# v2.net
KiCad netlist of a schematic drawn in EAGLE
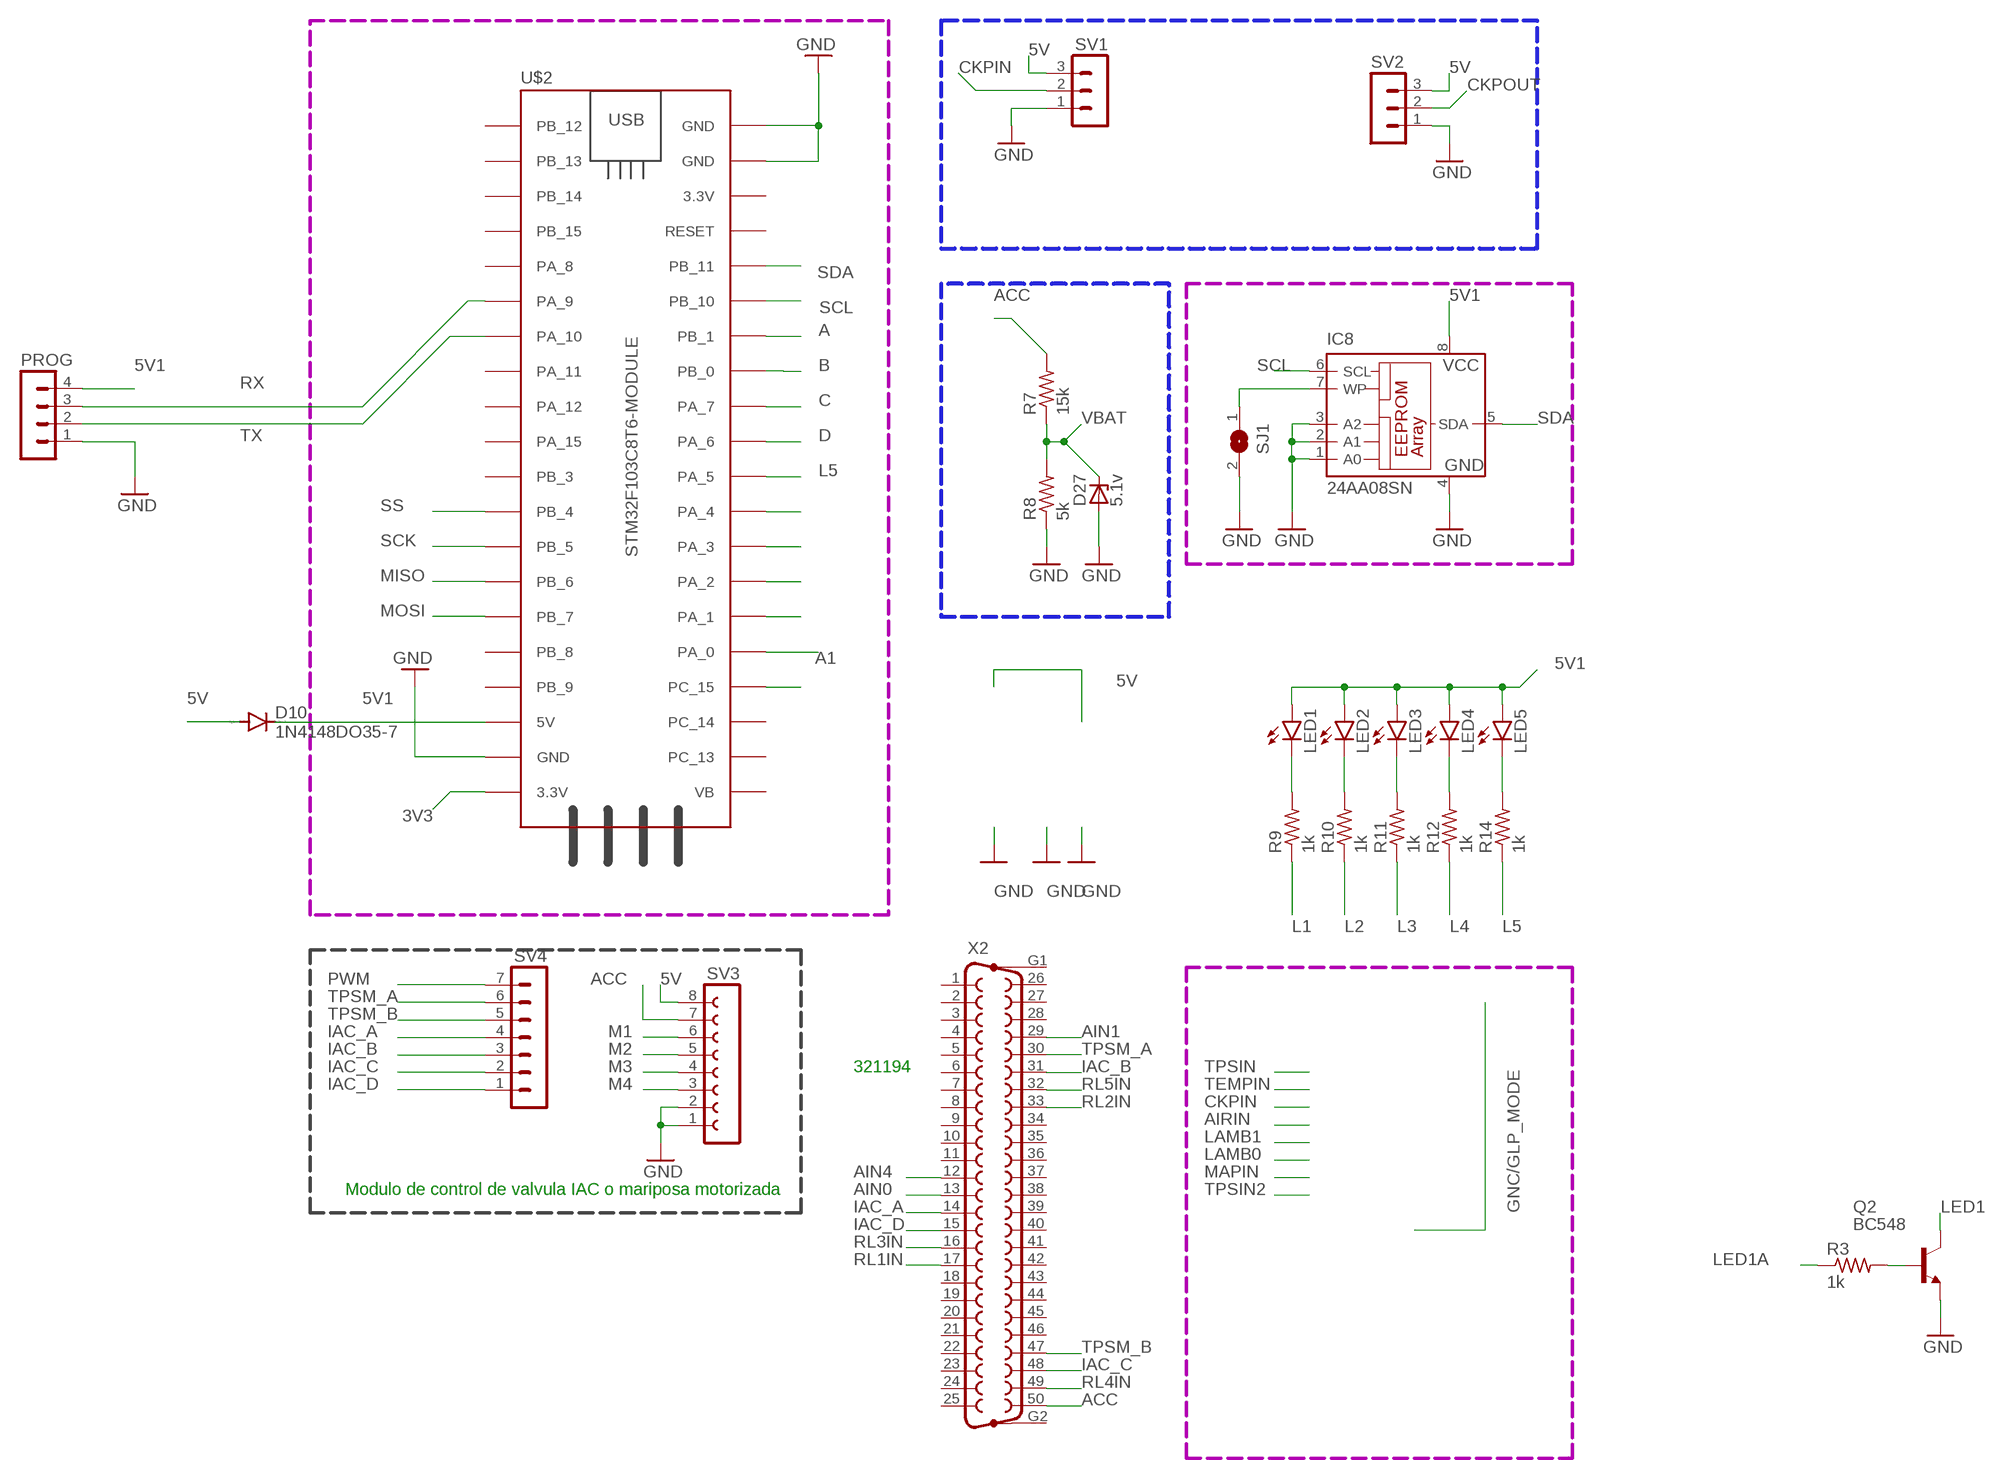
[diagram p0: schematic, sheet 1]
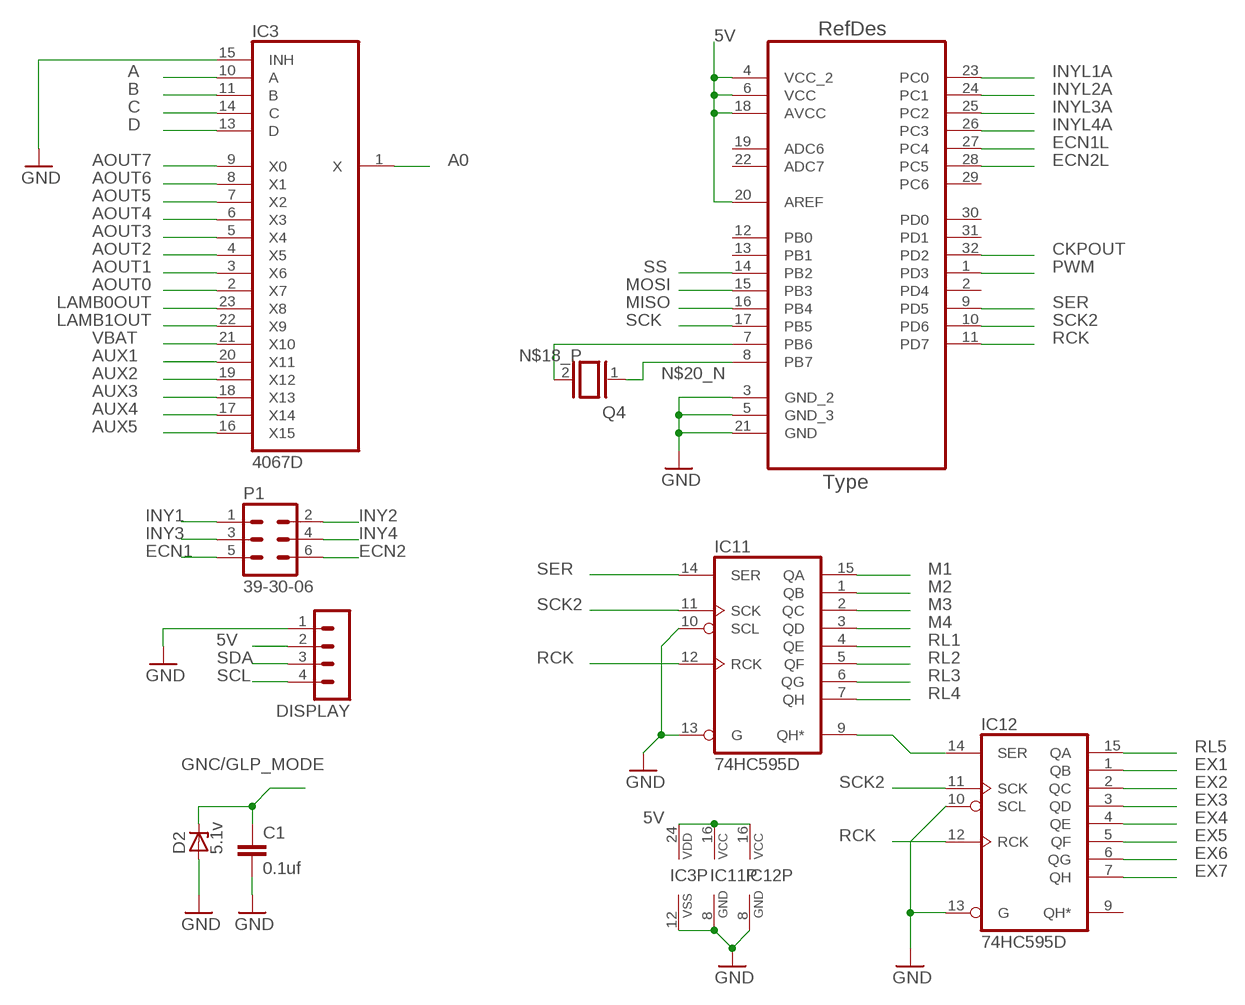
[diagram p1: schematic, sheet 2]
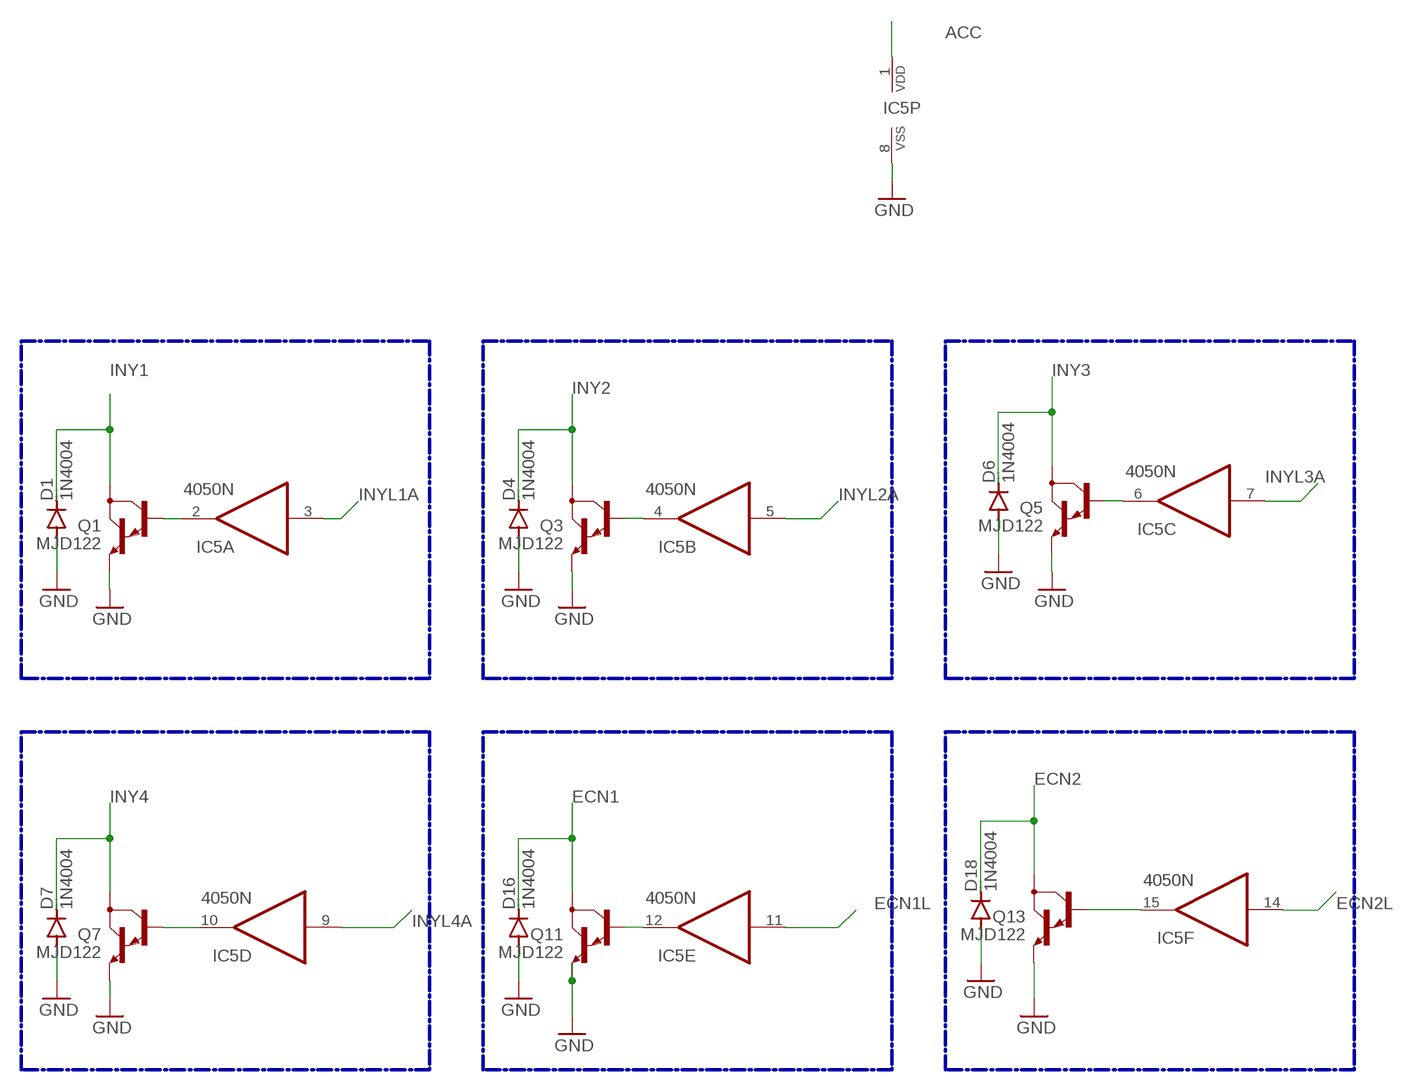
[diagram p2: schematic, sheet 3]
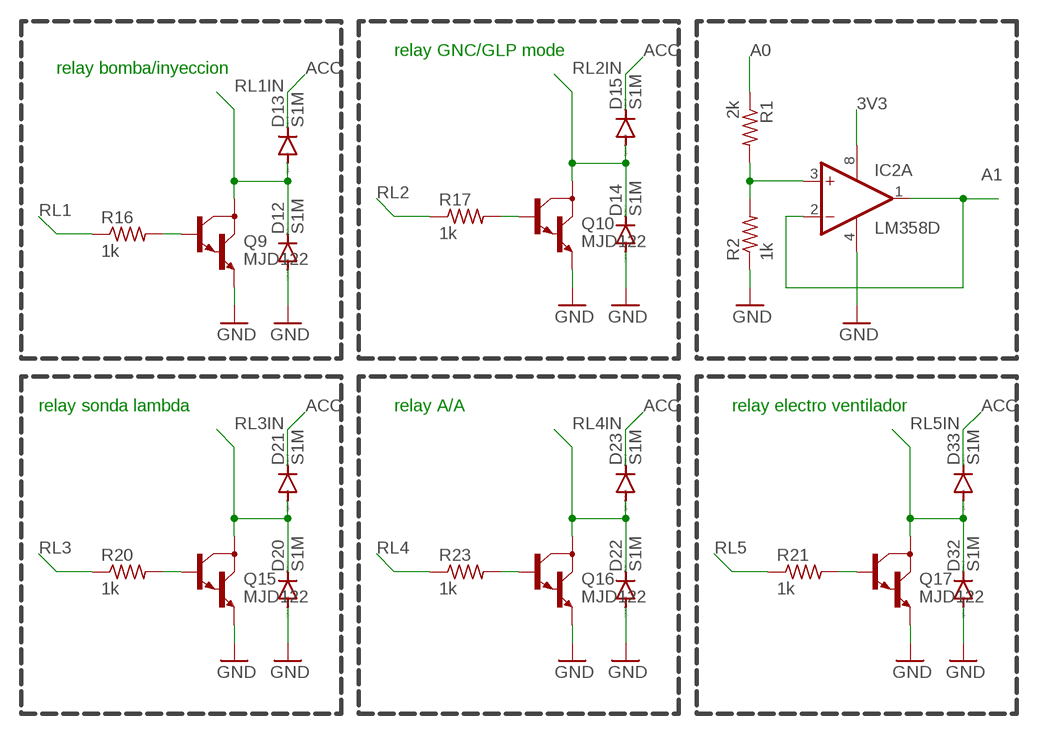
[diagram p3: schematic, sheet 4]
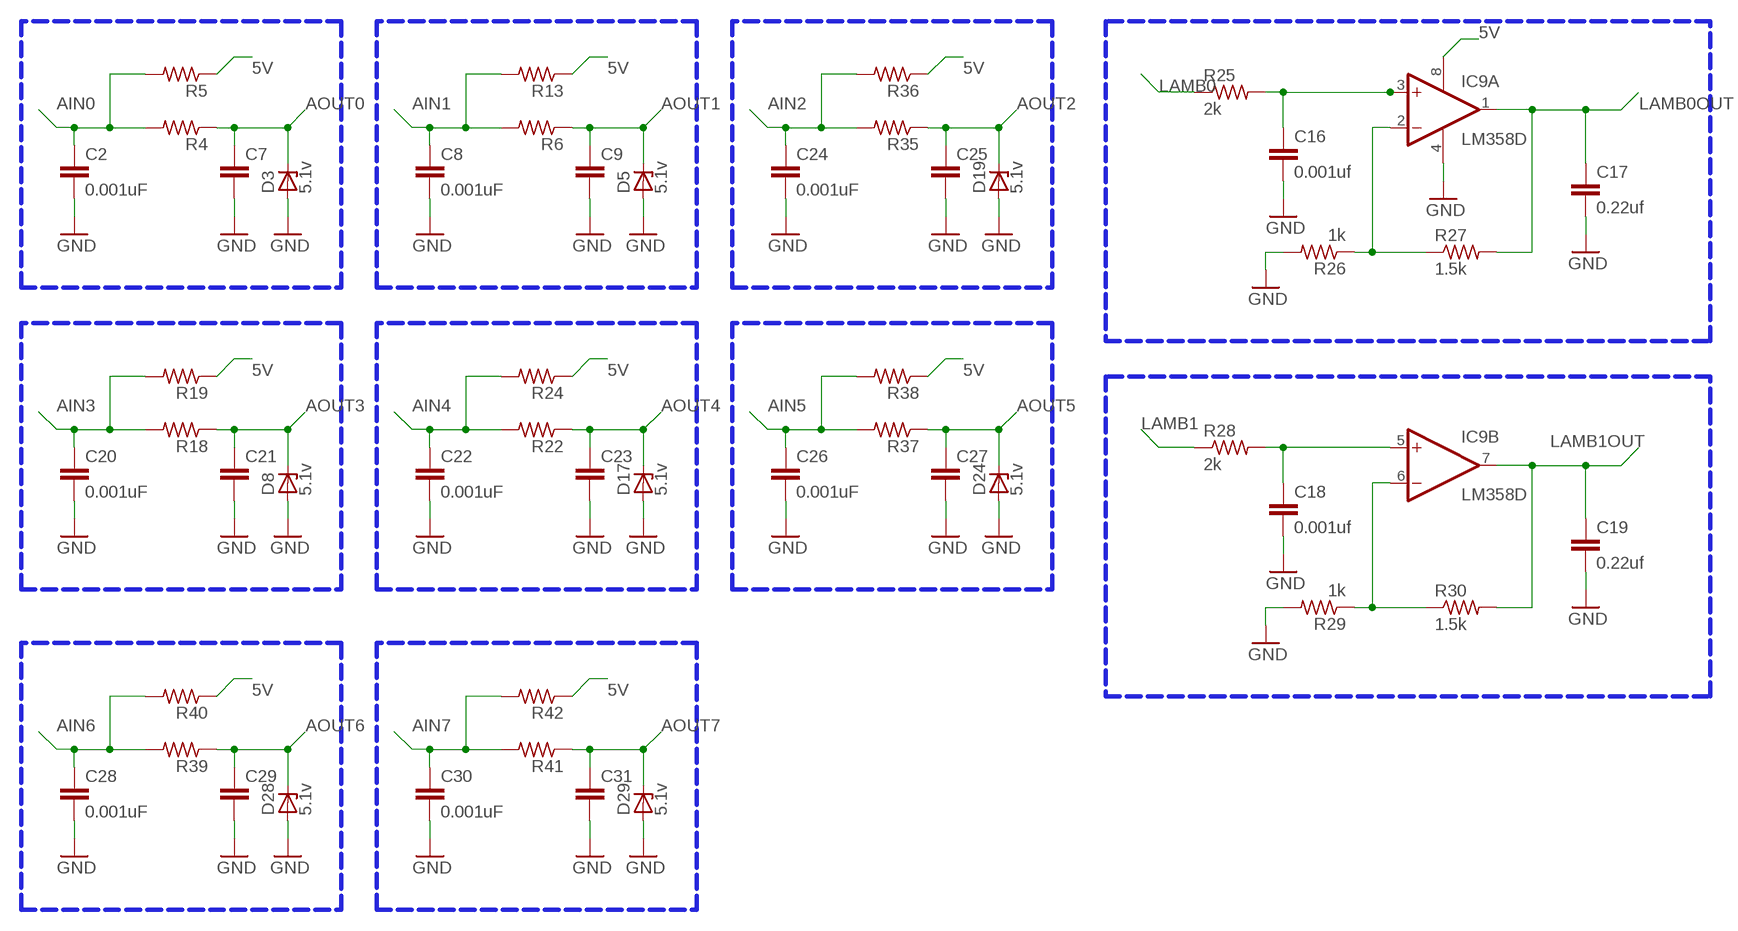
[diagram p4: schematic, sheet 5]
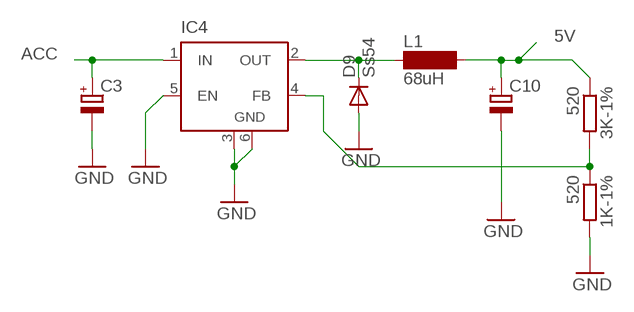
[diagram p5: schematic, sheet 6]

(export (version "E")
  (design (tool "Eeschema 10.0.6"))
  (components
    (comp (ref "D1")
      (value "1N4004")
      (footprint "eagle-import:DO41-10")
      (libsource (lib "eagle-import") (part "1N4004"))
    )
    (comp (ref "D4")
      (value "1N4004")
      (footprint "eagle-import:DO41-10")
      (libsource (lib "eagle-import") (part "1N4004"))
    )
    (comp (ref "D6")
      (value "1N4004")
      (footprint "eagle-import:DO41-10")
      (libsource (lib "eagle-import") (part "1N4004"))
    )
    (comp (ref "D7")
      (value "1N4004")
      (footprint "eagle-import:DO41-10")
      (libsource (lib "eagle-import") (part "1N4004"))
    )
    (comp (ref "D16")
      (value "1N4004")
      (footprint "eagle-import:DO41-10")
      (libsource (lib "eagle-import") (part "1N4004"))
    )
    (comp (ref "D18")
      (value "1N4004")
      (footprint "eagle-import:DO41-10")
      (libsource (lib "eagle-import") (part "1N4004"))
    )
    (comp (ref "IC5")
      (value "4050N")
      (footprint "eagle-import:DIL16")
      (libsource (lib "eagle-import") (part "4050N"))
    )
    (comp (ref "Q1")
      (value "MJD122")
      (footprint "eagle-import:DPAK")
      (fields (field (name "MF") "STMicroelectronics"))
      (libsource (lib "eagle-import") (part "MJD122"))
    )
    (comp (ref "Q3")
      (value "MJD122")
      (footprint "eagle-import:DPAK")
      (fields (field (name "MF") "STMicroelectronics"))
      (libsource (lib "eagle-import") (part "MJD122"))
    )
    (comp (ref "Q5")
      (value "MJD122")
      (footprint "eagle-import:DPAK")
      (fields (field (name "MF") "STMicroelectronics"))
      (libsource (lib "eagle-import") (part "MJD122"))
    )
    (comp (ref "Q7")
      (value "MJD122")
      (footprint "eagle-import:DPAK")
      (fields (field (name "MF") "STMicroelectronics"))
      (libsource (lib "eagle-import") (part "MJD122"))
    )
    (comp (ref "Q11")
      (value "MJD122")
      (footprint "eagle-import:DPAK")
      (fields (field (name "MF") "STMicroelectronics"))
      (libsource (lib "eagle-import") (part "MJD122"))
    )
    (comp (ref "Q13")
      (value "MJD122")
      (footprint "eagle-import:DPAK")
      (fields (field (name "MF") "STMicroelectronics"))
      (libsource (lib "eagle-import") (part "MJD122"))
    )
    (comp (ref "C2")
      (value "0.001uF")
      (footprint "eagle-import:C025-025X050")
      (libsource (lib "eagle-import") (part "C-EU025-025X050"))
    )
    (comp (ref "C7")
      (value "C-EU025-025X050")
      (footprint "eagle-import:C025-025X050")
      (libsource (lib "eagle-import") (part "C-EU025-025X050"))
    )
    (comp (ref "C8")
      (value "0.001uF")
      (footprint "eagle-import:C025-025X050")
      (libsource (lib "eagle-import") (part "C-EU025-025X050"))
    )
    (comp (ref "C9")
      (value "C-EU025-025X050")
      (footprint "eagle-import:C025-025X050")
      (libsource (lib "eagle-import") (part "C-EU025-025X050"))
    )
    (comp (ref "C16")
      (value "0.001uf")
      (footprint "eagle-import:C025-025X050")
      (libsource (lib "eagle-import") (part "C-EU025-025X050"))
    )
    (comp (ref "C17")
      (value "0.22uf")
      (footprint "eagle-import:C025-025X050")
      (libsource (lib "eagle-import") (part "C-EU025-025X050"))
    )
    (comp (ref "C18")
      (value "0.001uf")
      (footprint "eagle-import:C025-025X050")
      (libsource (lib "eagle-import") (part "C-EU025-025X050"))
    )
    (comp (ref "C19")
      (value "0.22uf")
      (footprint "eagle-import:C025-025X050")
      (libsource (lib "eagle-import") (part "C-EU025-025X050"))
    )
    (comp (ref "C20")
      (value "0.001uF")
      (footprint "eagle-import:C025-025X050")
      (libsource (lib "eagle-import") (part "C-EU025-025X050"))
    )
    (comp (ref "C21")
      (value "C-EU025-025X050")
      (footprint "eagle-import:C025-025X050")
      (libsource (lib "eagle-import") (part "C-EU025-025X050"))
    )
    (comp (ref "C22")
      (value "0.001uF")
      (footprint "eagle-import:C025-025X050")
      (libsource (lib "eagle-import") (part "C-EU025-025X050"))
    )
    (comp (ref "C23")
      (value "C-EU025-025X050")
      (footprint "eagle-import:C025-025X050")
      (libsource (lib "eagle-import") (part "C-EU025-025X050"))
    )
    (comp (ref "C24")
      (value "0.001uF")
      (footprint "eagle-import:C025-025X050")
      (libsource (lib "eagle-import") (part "C-EU025-025X050"))
    )
    (comp (ref "C25")
      (value "C-EU025-025X050")
      (footprint "eagle-import:C025-025X050")
      (libsource (lib "eagle-import") (part "C-EU025-025X050"))
    )
    (comp (ref "C26")
      (value "0.001uF")
      (footprint "eagle-import:C025-025X050")
      (libsource (lib "eagle-import") (part "C-EU025-025X050"))
    )
    (comp (ref "C27")
      (value "C-EU025-025X050")
      (footprint "eagle-import:C025-025X050")
      (libsource (lib "eagle-import") (part "C-EU025-025X050"))
    )
    (comp (ref "C28")
      (value "0.001uF")
      (footprint "eagle-import:C025-025X050")
      (libsource (lib "eagle-import") (part "C-EU025-025X050"))
    )
    (comp (ref "C29")
      (value "C-EU025-025X050")
      (footprint "eagle-import:C025-025X050")
      (libsource (lib "eagle-import") (part "C-EU025-025X050"))
    )
    (comp (ref "C30")
      (value "0.001uF")
      (footprint "eagle-import:C025-025X050")
      (libsource (lib "eagle-import") (part "C-EU025-025X050"))
    )
    (comp (ref "C31")
      (value "C-EU025-025X050")
      (footprint "eagle-import:C025-025X050")
      (libsource (lib "eagle-import") (part "C-EU025-025X050"))
    )
    (comp (ref "D3")
      (value "5.1v")
      (footprint "eagle-import:ZDIO-5")
      (libsource (lib "eagle-import") (part "ZENER-DIODEZD-5"))
    )
    (comp (ref "D5")
      (value "5.1v")
      (footprint "eagle-import:ZDIO-5")
      (libsource (lib "eagle-import") (part "ZENER-DIODEZD-5"))
    )
    (comp (ref "D8")
      (value "5.1v")
      (footprint "eagle-import:ZDIO-5")
      (libsource (lib "eagle-import") (part "ZENER-DIODEZD-5"))
    )
    (comp (ref "D17")
      (value "5.1v")
      (footprint "eagle-import:ZDIO-5")
      (libsource (lib "eagle-import") (part "ZENER-DIODEZD-5"))
    )
    (comp (ref "D19")
      (value "5.1v")
      (footprint "eagle-import:ZDIO-5")
      (libsource (lib "eagle-import") (part "ZENER-DIODEZD-5"))
    )
    (comp (ref "D24")
      (value "5.1v")
      (footprint "eagle-import:ZDIO-5")
      (libsource (lib "eagle-import") (part "ZENER-DIODEZD-5"))
    )
    (comp (ref "D28")
      (value "5.1v")
      (footprint "eagle-import:ZDIO-5")
      (libsource (lib "eagle-import") (part "ZENER-DIODEZD-5"))
    )
    (comp (ref "D29")
      (value "5.1v")
      (footprint "eagle-import:ZDIO-5")
      (libsource (lib "eagle-import") (part "ZENER-DIODEZD-5"))
    )
    (comp (ref "IC9")
      (value "LM358D")
      (footprint "eagle-import:SO08")
      (libsource (lib "eagle-import") (part "LM358D"))
    )
    (comp (ref "R4")
      (value "R-US_0204/5")
      (footprint "eagle-import:0204_5")
      (libsource (lib "eagle-import") (part "R-US_0204/5"))
    )
    (comp (ref "R5")
      (value "R-US_0204/5")
      (footprint "eagle-import:0204_5")
      (libsource (lib "eagle-import") (part "R-US_0204/5"))
    )
    (comp (ref "R6")
      (value "R-US_0204/5")
      (footprint "eagle-import:0204_5")
      (libsource (lib "eagle-import") (part "R-US_0204/5"))
    )
    (comp (ref "R13")
      (value "R-US_0204/5")
      (footprint "eagle-import:0204_5")
      (libsource (lib "eagle-import") (part "R-US_0204/5"))
    )
    (comp (ref "R18")
      (value "R-US_0204/5")
      (footprint "eagle-import:0204_5")
      (libsource (lib "eagle-import") (part "R-US_0204/5"))
    )
    (comp (ref "R19")
      (value "R-US_0204/5")
      (footprint "eagle-import:0204_5")
      (libsource (lib "eagle-import") (part "R-US_0204/5"))
    )
    (comp (ref "R22")
      (value "R-US_0204/5")
      (footprint "eagle-import:0204_5")
      (libsource (lib "eagle-import") (part "R-US_0204/5"))
    )
    (comp (ref "R24")
      (value "R-US_0204/5")
      (footprint "eagle-import:0204_5")
      (libsource (lib "eagle-import") (part "R-US_0204/5"))
    )
    (comp (ref "R25")
      (value "2k")
      (footprint "eagle-import:0204_5")
      (libsource (lib "eagle-import") (part "R-US_0204/5"))
    )
    (comp (ref "R26")
      (value "1k")
      (footprint "eagle-import:0204_5")
      (libsource (lib "eagle-import") (part "R-US_0204/5"))
    )
    (comp (ref "R27")
      (value "1.5k")
      (footprint "eagle-import:0204_5")
      (libsource (lib "eagle-import") (part "R-US_0204/5"))
    )
    (comp (ref "R28")
      (value "2k")
      (footprint "eagle-import:0204_5")
      (libsource (lib "eagle-import") (part "R-US_0204/5"))
    )
    (comp (ref "R29")
      (value "1k")
      (footprint "eagle-import:0204_5")
      (libsource (lib "eagle-import") (part "R-US_0204/5"))
    )
    (comp (ref "R30")
      (value "1.5k")
      (footprint "eagle-import:0204_5")
      (libsource (lib "eagle-import") (part "R-US_0204/5"))
    )
    (comp (ref "R35")
      (value "R-US_0204/5")
      (footprint "eagle-import:0204_5")
      (libsource (lib "eagle-import") (part "R-US_0204/5"))
    )
    (comp (ref "R36")
      (value "R-US_0204/5")
      (footprint "eagle-import:0204_5")
      (libsource (lib "eagle-import") (part "R-US_0204/5"))
    )
    (comp (ref "R37")
      (value "R-US_0204/5")
      (footprint "eagle-import:0204_5")
      (libsource (lib "eagle-import") (part "R-US_0204/5"))
    )
    (comp (ref "R38")
      (value "R-US_0204/5")
      (footprint "eagle-import:0204_5")
      (libsource (lib "eagle-import") (part "R-US_0204/5"))
    )
    (comp (ref "R39")
      (value "R-US_0204/5")
      (footprint "eagle-import:0204_5")
      (libsource (lib "eagle-import") (part "R-US_0204/5"))
    )
    (comp (ref "R40")
      (value "R-US_0204/5")
      (footprint "eagle-import:0204_5")
      (libsource (lib "eagle-import") (part "R-US_0204/5"))
    )
    (comp (ref "R41")
      (value "R-US_0204/5")
      (footprint "eagle-import:0204_5")
      (libsource (lib "eagle-import") (part "R-US_0204/5"))
    )
    (comp (ref "R42")
      (value "R-US_0204/5")
      (footprint "eagle-import:0204_5")
      (libsource (lib "eagle-import") (part "R-US_0204/5"))
    )
    (comp (ref "D12")
      (value "S1M")
      (footprint "eagle-import:SMA")
      (libsource (lib "eagle-import") (part "S1M"))
    )
    (comp (ref "D13")
      (value "S1M")
      (footprint "eagle-import:SMA")
      (libsource (lib "eagle-import") (part "S1M"))
    )
    (comp (ref "D14")
      (value "S1M")
      (footprint "eagle-import:SMA")
      (libsource (lib "eagle-import") (part "S1M"))
    )
    (comp (ref "D15")
      (value "S1M")
      (footprint "eagle-import:SMA")
      (libsource (lib "eagle-import") (part "S1M"))
    )
    (comp (ref "D20")
      (value "S1M")
      (footprint "eagle-import:SMA")
      (libsource (lib "eagle-import") (part "S1M"))
    )
    (comp (ref "D21")
      (value "S1M")
      (footprint "eagle-import:SMA")
      (libsource (lib "eagle-import") (part "S1M"))
    )
    (comp (ref "D22")
      (value "S1M")
      (footprint "eagle-import:SMA")
      (libsource (lib "eagle-import") (part "S1M"))
    )
    (comp (ref "D23")
      (value "S1M")
      (footprint "eagle-import:SMA")
      (libsource (lib "eagle-import") (part "S1M"))
    )
    (comp (ref "D32")
      (value "S1M")
      (footprint "eagle-import:SMA")
      (libsource (lib "eagle-import") (part "S1M"))
    )
    (comp (ref "D33")
      (value "S1M")
      (footprint "eagle-import:SMA")
      (libsource (lib "eagle-import") (part "S1M"))
    )
    (comp (ref "IC2")
      (value "LM358D")
      (footprint "eagle-import:SO08")
      (libsource (lib "eagle-import") (part "LM358D"))
    )
    (comp (ref "Q9")
      (value "MJD122")
      (footprint "eagle-import:DPAK")
      (fields (field (name "MF") "STMicroelectronics"))
      (libsource (lib "eagle-import") (part "MJD122"))
    )
    (comp (ref "Q10")
      (value "MJD122")
      (footprint "eagle-import:DPAK")
      (fields (field (name "MF") "STMicroelectronics"))
      (libsource (lib "eagle-import") (part "MJD122"))
    )
    (comp (ref "Q15")
      (value "MJD122")
      (footprint "eagle-import:DPAK")
      (fields (field (name "MF") "STMicroelectronics"))
      (libsource (lib "eagle-import") (part "MJD122"))
    )
    (comp (ref "Q16")
      (value "MJD122")
      (footprint "eagle-import:DPAK")
      (fields (field (name "MF") "STMicroelectronics"))
      (libsource (lib "eagle-import") (part "MJD122"))
    )
    (comp (ref "Q17")
      (value "MJD122")
      (footprint "eagle-import:DPAK")
      (fields (field (name "MF") "STMicroelectronics"))
      (libsource (lib "eagle-import") (part "MJD122"))
    )
    (comp (ref "R1")
      (value "2k")
      (footprint "eagle-import:0204_5")
      (libsource (lib "eagle-import") (part "R-US_0204/5"))
    )
    (comp (ref "R2")
      (value "1k")
      (footprint "eagle-import:0204_5")
      (libsource (lib "eagle-import") (part "R-US_0204/5"))
    )
    (comp (ref "R16")
      (value "1k")
      (footprint "eagle-import:0204_5")
      (libsource (lib "eagle-import") (part "R-US_0204/5"))
    )
    (comp (ref "R17")
      (value "1k")
      (footprint "eagle-import:0204_5")
      (libsource (lib "eagle-import") (part "R-US_0204/5"))
    )
    (comp (ref "R20")
      (value "1k")
      (footprint "eagle-import:0204_5")
      (libsource (lib "eagle-import") (part "R-US_0204/5"))
    )
    (comp (ref "R21")
      (value "1k")
      (footprint "eagle-import:0204_5")
      (libsource (lib "eagle-import") (part "R-US_0204/5"))
    )
    (comp (ref "R23")
      (value "1k")
      (footprint "eagle-import:0204_5")
      (libsource (lib "eagle-import") (part "R-US_0204/5"))
    )
    (comp (ref "C1")
      (value "0.1uf")
      (footprint "eagle-import:C025-025X050")
      (libsource (lib "eagle-import") (part "C-EU025-025X050"))
    )
    (comp (ref "D2")
      (value "5.1v")
      (footprint "eagle-import:ZDIO-5")
      (libsource (lib "eagle-import") (part "ZENER-DIODEZD-5"))
    )
    (comp (ref "DISPLAY")
      (value "MA04-1")
      (footprint "eagle-import:MA04-1")
      (libsource (lib "eagle-import") (part "MA04-1"))
    )
    (comp (ref "IC3")
      (value "4067D")
      (footprint "eagle-import:SO24W")
      (libsource (lib "eagle-import") (part "4067D"))
    )
    (comp (ref "IC11")
      (value "74HC595D")
      (footprint "eagle-import:SO16")
      (libsource (lib "eagle-import") (part "74595DHC"))
    )
    (comp (ref "IC12")
      (value "74HC595D")
      (footprint "eagle-import:SO16")
      (libsource (lib "eagle-import") (part "74595DHC"))
    )
    (comp (ref "P1")
      (value "39-30-06")
      (footprint "eagle-import:39-30-_06_")
      (libsource (lib "eagle-import") (part "39-30-?06?"))
    )
    (comp (ref "Q4")
      (value "XTAL/S")
      (footprint "eagle-import:QS")
      (libsource (lib "eagle-import") (part "XTAL/S"))
    )
    (comp (ref "U1")
      (value "ATMEGA328P-AU")
      (footprint "eagle-import:QFP80P900X900X120-32N")
      (libsource (lib "eagle-import") (part "ATMEGA328P-AU"))
    )
    (comp (ref "1K-1%")
      (value "520")
      (footprint "eagle-import:0204_7")
      (libsource (lib "eagle-import") (part "R-EU_0204/7"))
    )
    (comp (ref "3K-1%")
      (value "520")
      (footprint "eagle-import:0204_7")
      (libsource (lib "eagle-import") (part "R-EU_0204/7"))
    )
    (comp (ref "C3")
      (value "CPOL-EUE3.5-8")
      (footprint "eagle-import:E3,5-8")
      (libsource (lib "eagle-import") (part "CPOL-EUE3.5-8"))
    )
    (comp (ref "C10")
      (value "CPOL-EUE3.5-8")
      (footprint "eagle-import:E3,5-8")
      (libsource (lib "eagle-import") (part "CPOL-EUE3.5-8"))
    )
    (comp (ref "D9")
      (value "Ss54")
      (footprint "eagle-import:DO214AC")
      (fields (field (name "MF") "Fairchild") (field (name "MPN") "S1A"))
      (libsource (lib "eagle-import") (part "S1A"))
    )
    (comp (ref "IC4")
      (value "LM2596S")
      (footprint "eagle-import:TO263-5")
      (libsource (lib "eagle-import") (part "LM2596S"))
    )
    (comp (ref "L1")
      (value "68uH")
      (footprint "eagle-import:SD12-680")
      (fields (field (name "MF") "BUSSMANN") (field (name "MPN") "SD12-680"))
      (libsource (lib "eagle-import") (part "SD12-680"))
    )
    (comp (ref "D10")
      (value "1N4148DO35-7")
      (footprint "eagle-import:DO35-7")
      (libsource (lib "eagle-import") (part "1N4148DO35-7"))
    )
    (comp (ref "D27")
      (value "5.1v")
      (footprint "eagle-import:ZDIO-5")
      (libsource (lib "eagle-import") (part "ZENER-DIODEZD-5"))
    )
    (comp (ref "IC8")
      (value "24AA08SN")
      (footprint "eagle-import:SO-08")
      (fields (field (name "MF") "MICROCHIP") (field (name "MPN") "24AA08-I/SN"))
      (libsource (lib "eagle-import") (part "24SNAA08"))
    )
    (comp (ref "LED1")
      (value "LED3MM")
      (footprint "eagle-import:LED3MM")
      (libsource (lib "eagle-import") (part "LED3MM"))
    )
    (comp (ref "LED2")
      (value "LED3MM")
      (footprint "eagle-import:LED3MM")
      (libsource (lib "eagle-import") (part "LED3MM"))
    )
    (comp (ref "LED3")
      (value "LED3MM")
      (footprint "eagle-import:LED3MM")
      (libsource (lib "eagle-import") (part "LED3MM"))
    )
    (comp (ref "LED4")
      (value "LED3MM")
      (footprint "eagle-import:LED3MM")
      (libsource (lib "eagle-import") (part "LED3MM"))
    )
    (comp (ref "LED5")
      (value "LED3MM")
      (footprint "eagle-import:LED3MM")
      (libsource (lib "eagle-import") (part "LED3MM"))
    )
    (comp (ref "PROG")
      (value "MA04-1")
      (footprint "eagle-import:MA04-1")
      (libsource (lib "eagle-import") (part "MA04-1"))
    )
    (comp (ref "Q2")
      (value "BC548")
      (footprint "eagle-import:TO92-EBC")
      (libsource (lib "eagle-import") (part "BC548"))
    )
    (comp (ref "R3")
      (value "1k")
      (footprint "eagle-import:0204_5")
      (libsource (lib "eagle-import") (part "R-US_0204/5"))
    )
    (comp (ref "R7")
      (value "15k")
      (footprint "eagle-import:0204_5")
      (libsource (lib "eagle-import") (part "R-US_0204/5"))
    )
    (comp (ref "R8")
      (value "5k")
      (footprint "eagle-import:0204_5")
      (libsource (lib "eagle-import") (part "R-US_0204/5"))
    )
    (comp (ref "R9")
      (value "1k")
      (footprint "eagle-import:0204_5")
      (libsource (lib "eagle-import") (part "R-US_0204/5"))
    )
    (comp (ref "R10")
      (value "1k")
      (footprint "eagle-import:0204_5")
      (libsource (lib "eagle-import") (part "R-US_0204/5"))
    )
    (comp (ref "R11")
      (value "1k")
      (footprint "eagle-import:0204_5")
      (libsource (lib "eagle-import") (part "R-US_0204/5"))
    )
    (comp (ref "R12")
      (value "1k")
      (footprint "eagle-import:0204_5")
      (libsource (lib "eagle-import") (part "R-US_0204/5"))
    )
    (comp (ref "R14")
      (value "1k")
      (footprint "eagle-import:0204_5")
      (libsource (lib "eagle-import") (part "R-US_0204/5"))
    )
    (comp (ref "SJ1")
      (value "SJW")
      (footprint "eagle-import:SJW")
      (libsource (lib "eagle-import") (part "SJW"))
    )
    (comp (ref "SV1")
      (value "MA03-1")
      (footprint "eagle-import:MA03-1")
      (libsource (lib "eagle-import") (part "MA03-1"))
    )
    (comp (ref "SV2")
      (value "MA03-1")
      (footprint "eagle-import:MA03-1")
      (libsource (lib "eagle-import") (part "MA03-1"))
    )
    (comp (ref "SV3")
      (value "FE08-1")
      (footprint "eagle-import:FE08")
      (libsource (lib "eagle-import") (part "FE08-1"))
    )
    (comp (ref "SV4")
      (value "MA07-1")
      (footprint "eagle-import:MA07-1")
      (libsource (lib "eagle-import") (part "MA07-1"))
    )
    (comp (ref "U$2")
      (value "STM32F103C8T6-MODULE")
      (footprint "eagle-import:STM32F103C8T6-MODULE")
      (libsource (lib "eagle-import") (part "STM32F103C8T6-MODULE"))
    )
    (comp (ref "X2")
      (value "F50HP")
      (footprint "eagle-import:F50HP")
      (libsource (lib "eagle-import") (part "F50HP"))
    )
  )
  (nets
    (net (code "3") (name "3V3") (class "Default")
      (node (ref "IC2") (pin "8") (pinfunction "V+_8") (pintype "power_in"))
      (node (ref "U$2") (pin "3.3V_1") (pinfunction "3.3V_3.3V_1") (pintype "bidirectional"))
    )
    (net (code "4") (name "5V") (class "Default")
      (node (ref "3K-1%") (pin "1") (pinfunction "1_1") (pintype "passive"))
      (node (ref "C10") (pin "+") (pinfunction "+_+") (pintype "passive"))
      (node (ref "D10") (pin "A") (pinfunction "A_A") (pintype "passive"))
      (node (ref "DISPLAY") (pin "2") (pinfunction "2_2") (pintype "passive"))
      (node (ref "IC11") (pin "16") (pinfunction "VCC_16") (pintype "power_in"))
      (node (ref "IC12") (pin "16") (pinfunction "VCC_16") (pintype "power_in"))
      (node (ref "IC3") (pin "24") (pinfunction "VDD_24") (pintype "power_in"))
      (node (ref "IC9") (pin "8") (pinfunction "V+_8") (pintype "power_in"))
      (node (ref "L1") (pin "2") (pinfunction "2_2") (pintype "passive"))
      (node (ref "R13") (pin "1") (pinfunction "1_1") (pintype "passive"))
      (node (ref "R19") (pin "1") (pinfunction "1_1") (pintype "passive"))
      (node (ref "R24") (pin "1") (pinfunction "1_1") (pintype "passive"))
      (node (ref "R36") (pin "1") (pinfunction "1_1") (pintype "passive"))
      (node (ref "R38") (pin "1") (pinfunction "1_1") (pintype "passive"))
      (node (ref "R40") (pin "1") (pinfunction "1_1") (pintype "passive"))
      (node (ref "R42") (pin "1") (pinfunction "1_1") (pintype "passive"))
      (node (ref "R5") (pin "1") (pinfunction "1_1") (pintype "passive"))
      (node (ref "SV1") (pin "3") (pinfunction "3_3") (pintype "passive"))
      (node (ref "SV2") (pin "3") (pinfunction "3_3") (pintype "passive"))
      (node (ref "SV3") (pin "8") (pinfunction "8_8") (pintype "passive"))
      (node (ref "U1") (pin "18") (pinfunction "AVCC_18") (pintype "power_in"))
      (node (ref "U1") (pin "20") (pinfunction "AREF_20") (pintype "input"))
      (node (ref "U1") (pin "4") (pinfunction "VCC_2_4") (pintype "power_in"))
      (node (ref "U1") (pin "6") (pinfunction "VCC_6") (pintype "power_in"))
    )
    (net (code "5") (name "5V1") (class "Default")
      (node (ref "D10") (pin "C") (pinfunction "C_C") (pintype "passive"))
      (node (ref "IC8") (pin "8") (pinfunction "VCC_8") (pintype "power_in"))
      (node (ref "LED1") (pin "A") (pinfunction "A_A") (pintype "passive"))
      (node (ref "LED2") (pin "A") (pinfunction "A_A") (pintype "passive"))
      (node (ref "LED3") (pin "A") (pinfunction "A_A") (pintype "passive"))
      (node (ref "LED4") (pin "A") (pinfunction "A_A") (pintype "passive"))
      (node (ref "LED5") (pin "A") (pinfunction "A_A") (pintype "passive"))
      (node (ref "PROG") (pin "4") (pinfunction "4_4") (pintype "passive"))
      (node (ref "U$2") (pin "5V") (pinfunction "5V_5V") (pintype "bidirectional"))
    )
    (net (code "6") (name "A") (class "Default")
      (node (ref "IC3") (pin "10") (pinfunction "A_10") (pintype "input"))
      (node (ref "U$2") (pin "PB_1") (pinfunction "PB_1_PB_1") (pintype "bidirectional"))
    )
    (net (code "7") (name "A0") (class "Default")
      (node (ref "IC3") (pin "1") (pinfunction "X_1") (pintype "output"))
      (node (ref "R1") (pin "1") (pinfunction "1_1") (pintype "passive"))
    )
    (net (code "8") (name "A1") (class "Default")
      (node (ref "IC2") (pin "1") (pinfunction "OUT_1") (pintype "output"))
      (node (ref "IC2") (pin "2") (pinfunction "-IN_2") (pintype "input"))
      (node (ref "U$2") (pin "PA_0") (pinfunction "PA_0_PA_0") (pintype "bidirectional"))
    )
    (net (code "9") (name "ACC") (class "Default")
      (node (ref "C3") (pin "+") (pinfunction "+_+") (pintype "passive"))
      (node (ref "D13") (pin "C") (pinfunction "C_C") (pintype "passive"))
      (node (ref "D15") (pin "C") (pinfunction "C_C") (pintype "passive"))
      (node (ref "D21") (pin "C") (pinfunction "C_C") (pintype "passive"))
      (node (ref "D23") (pin "C") (pinfunction "C_C") (pintype "passive"))
      (node (ref "D33") (pin "C") (pinfunction "C_C") (pintype "passive"))
      (node (ref "IC4") (pin "1") (pinfunction "IN_1") (pintype "input"))
      (node (ref "IC5") (pin "1") (pinfunction "VDD_1") (pintype "power_in"))
      (node (ref "R7") (pin "2") (pinfunction "2_2") (pintype "passive"))
      (node (ref "SV3") (pin "7") (pinfunction "7_7") (pintype "passive"))
      (node (ref "X2") (pin "50") (pinfunction "50_50") (pintype "passive"))
    )
    (net (code "10") (name "AIN0") (class "Default")
      (node (ref "C2") (pin "1") (pinfunction "1_1") (pintype "passive"))
      (node (ref "R4") (pin "2") (pinfunction "2_2") (pintype "passive"))
      (node (ref "R5") (pin "2") (pinfunction "2_2") (pintype "passive"))
      (node (ref "X2") (pin "13") (pinfunction "13_13") (pintype "passive"))
    )
    (net (code "11") (name "AIN1") (class "Default")
      (node (ref "C8") (pin "1") (pinfunction "1_1") (pintype "passive"))
      (node (ref "R13") (pin "2") (pinfunction "2_2") (pintype "passive"))
      (node (ref "R6") (pin "2") (pinfunction "2_2") (pintype "passive"))
      (node (ref "X2") (pin "29") (pinfunction "29_29") (pintype "passive"))
    )
    (net (code "12") (name "AIN2") (class "Default")
      (node (ref "C24") (pin "1") (pinfunction "1_1") (pintype "passive"))
      (node (ref "R35") (pin "2") (pinfunction "2_2") (pintype "passive"))
      (node (ref "R36") (pin "2") (pinfunction "2_2") (pintype "passive"))
    )
    (net (code "13") (name "AIN3") (class "Default")
      (node (ref "C20") (pin "1") (pinfunction "1_1") (pintype "passive"))
      (node (ref "R18") (pin "2") (pinfunction "2_2") (pintype "passive"))
      (node (ref "R19") (pin "2") (pinfunction "2_2") (pintype "passive"))
    )
    (net (code "14") (name "AIN4") (class "Default")
      (node (ref "C22") (pin "1") (pinfunction "1_1") (pintype "passive"))
      (node (ref "R22") (pin "2") (pinfunction "2_2") (pintype "passive"))
      (node (ref "R24") (pin "2") (pinfunction "2_2") (pintype "passive"))
      (node (ref "X2") (pin "12") (pinfunction "12_12") (pintype "passive"))
    )
    (net (code "15") (name "AIN5") (class "Default")
      (node (ref "C26") (pin "1") (pinfunction "1_1") (pintype "passive"))
      (node (ref "R37") (pin "2") (pinfunction "2_2") (pintype "passive"))
      (node (ref "R38") (pin "2") (pinfunction "2_2") (pintype "passive"))
    )
    (net (code "16") (name "AIN6") (class "Default")
      (node (ref "C28") (pin "1") (pinfunction "1_1") (pintype "passive"))
      (node (ref "R39") (pin "2") (pinfunction "2_2") (pintype "passive"))
      (node (ref "R40") (pin "2") (pinfunction "2_2") (pintype "passive"))
    )
    (net (code "17") (name "AIN7") (class "Default")
      (node (ref "C30") (pin "1") (pinfunction "1_1") (pintype "passive"))
      (node (ref "R41") (pin "2") (pinfunction "2_2") (pintype "passive"))
      (node (ref "R42") (pin "2") (pinfunction "2_2") (pintype "passive"))
    )
    (net (code "19") (name "AOUT0") (class "Default")
      (node (ref "C7") (pin "1") (pinfunction "1_1") (pintype "passive"))
      (node (ref "D3") (pin "C") (pinfunction "C_C") (pintype "passive"))
      (node (ref "IC3") (pin "2") (pinfunction "X7_2") (pintype "input"))
      (node (ref "R4") (pin "1") (pinfunction "1_1") (pintype "passive"))
    )
    (net (code "20") (name "AOUT1") (class "Default")
      (node (ref "C9") (pin "1") (pinfunction "1_1") (pintype "passive"))
      (node (ref "D5") (pin "C") (pinfunction "C_C") (pintype "passive"))
      (node (ref "IC3") (pin "3") (pinfunction "X6_3") (pintype "input"))
      (node (ref "R6") (pin "1") (pinfunction "1_1") (pintype "passive"))
    )
    (net (code "21") (name "AOUT2") (class "Default")
      (node (ref "C25") (pin "1") (pinfunction "1_1") (pintype "passive"))
      (node (ref "D19") (pin "C") (pinfunction "C_C") (pintype "passive"))
      (node (ref "IC3") (pin "4") (pinfunction "X5_4") (pintype "input"))
      (node (ref "R35") (pin "1") (pinfunction "1_1") (pintype "passive"))
    )
    (net (code "22") (name "AOUT3") (class "Default")
      (node (ref "C21") (pin "1") (pinfunction "1_1") (pintype "passive"))
      (node (ref "D8") (pin "C") (pinfunction "C_C") (pintype "passive"))
      (node (ref "IC3") (pin "5") (pinfunction "X4_5") (pintype "input"))
      (node (ref "R18") (pin "1") (pinfunction "1_1") (pintype "passive"))
    )
    (net (code "23") (name "AOUT4") (class "Default")
      (node (ref "C23") (pin "1") (pinfunction "1_1") (pintype "passive"))
      (node (ref "D17") (pin "C") (pinfunction "C_C") (pintype "passive"))
      (node (ref "IC3") (pin "6") (pinfunction "X3_6") (pintype "input"))
      (node (ref "R22") (pin "1") (pinfunction "1_1") (pintype "passive"))
    )
    (net (code "24") (name "AOUT5") (class "Default")
      (node (ref "C27") (pin "1") (pinfunction "1_1") (pintype "passive"))
      (node (ref "D24") (pin "C") (pinfunction "C_C") (pintype "passive"))
      (node (ref "IC3") (pin "7") (pinfunction "X2_7") (pintype "input"))
      (node (ref "R37") (pin "1") (pinfunction "1_1") (pintype "passive"))
    )
    (net (code "25") (name "AOUT6") (class "Default")
      (node (ref "C29") (pin "1") (pinfunction "1_1") (pintype "passive"))
      (node (ref "D28") (pin "C") (pinfunction "C_C") (pintype "passive"))
      (node (ref "IC3") (pin "8") (pinfunction "X1_8") (pintype "input"))
      (node (ref "R39") (pin "1") (pinfunction "1_1") (pintype "passive"))
    )
    (net (code "26") (name "AOUT7") (class "Default")
      (node (ref "C31") (pin "1") (pinfunction "1_1") (pintype "passive"))
      (node (ref "D29") (pin "C") (pinfunction "C_C") (pintype "passive"))
      (node (ref "IC3") (pin "9") (pinfunction "X0_9") (pintype "input"))
      (node (ref "R41") (pin "1") (pinfunction "1_1") (pintype "passive"))
    )
    (net (code "27") (name "AUX1") (class "Default")
      (node (ref "IC3") (pin "20") (pinfunction "X11_20") (pintype "input"))
    )
    (net (code "28") (name "AUX2") (class "Default")
      (node (ref "IC3") (pin "19") (pinfunction "X12_19") (pintype "input"))
    )
    (net (code "29") (name "AUX3") (class "Default")
      (node (ref "IC3") (pin "18") (pinfunction "X13_18") (pintype "input"))
    )
    (net (code "30") (name "AUX4") (class "Default")
      (node (ref "IC3") (pin "17") (pinfunction "X14_17") (pintype "input"))
    )
    (net (code "31") (name "AUX5") (class "Default")
      (node (ref "IC3") (pin "16") (pinfunction "X15_16") (pintype "input"))
    )
    (net (code "32") (name "B") (class "Default")
      (node (ref "IC3") (pin "11") (pinfunction "B_11") (pintype "input"))
      (node (ref "U$2") (pin "PB_0") (pinfunction "PB_0_PB_0") (pintype "bidirectional"))
    )
    (net (code "33") (name "C") (class "Default")
      (node (ref "IC3") (pin "14") (pinfunction "C_14") (pintype "input"))
      (node (ref "U$2") (pin "PA_7") (pinfunction "PA_7_PA_7") (pintype "bidirectional"))
    )
    (net (code "34") (name "CKPIN") (class "Default")
      (node (ref "SV1") (pin "2") (pinfunction "2_2") (pintype "passive"))
    )
    (net (code "35") (name "CKPOUT") (class "Default")
      (node (ref "SV2") (pin "2") (pinfunction "2_2") (pintype "passive"))
      (node (ref "U1") (pin "32") (pinfunction "PD2_32") (pintype "bidirectional"))
    )
    (net (code "36") (name "D") (class "Default")
      (node (ref "IC3") (pin "13") (pinfunction "D_13") (pintype "input"))
      (node (ref "U$2") (pin "PA_6") (pinfunction "PA_6_PA_6") (pintype "bidirectional"))
    )
    (net (code "37") (name "ECN1") (class "Default")
      (node (ref "D16") (pin "C") (pinfunction "C_C") (pintype "passive"))
      (node (ref "P1") (pin "5") (pinfunction "5_5") (pintype "passive"))
      (node (ref "Q11") (pin "4") (pinfunction "C_4") (pintype "passive"))
    )
    (net (code "38") (name "ECN1L") (class "Default")
      (node (ref "IC5") (pin "11") (pinfunction "I_11") (pintype "input"))
      (node (ref "U1") (pin "27") (pinfunction "PC4_27") (pintype "bidirectional"))
    )
    (net (code "39") (name "ECN2") (class "Default")
      (node (ref "D18") (pin "C") (pinfunction "C_C") (pintype "passive"))
      (node (ref "P1") (pin "6") (pinfunction "6_6") (pintype "passive"))
      (node (ref "Q13") (pin "4") (pinfunction "C_4") (pintype "passive"))
    )
    (net (code "40") (name "ECN2L") (class "Default")
      (node (ref "IC5") (pin "14") (pinfunction "I_14") (pintype "input"))
      (node (ref "U1") (pin "28") (pinfunction "PC5_28") (pintype "bidirectional"))
    )
    (net (code "41") (name "EX1") (class "Default")
      (node (ref "IC12") (pin "1") (pinfunction "QB_1") (pintype "tri_state"))
    )
    (net (code "42") (name "EX2") (class "Default")
      (node (ref "IC12") (pin "2") (pinfunction "QC_2") (pintype "tri_state"))
    )
    (net (code "43") (name "EX3") (class "Default")
      (node (ref "IC12") (pin "3") (pinfunction "QD_3") (pintype "tri_state"))
    )
    (net (code "44") (name "EX4") (class "Default")
      (node (ref "IC12") (pin "4") (pinfunction "QE_4") (pintype "tri_state"))
    )
    (net (code "45") (name "EX5") (class "Default")
      (node (ref "IC12") (pin "5") (pinfunction "QF_5") (pintype "tri_state"))
    )
    (net (code "46") (name "EX6") (class "Default")
      (node (ref "IC12") (pin "6") (pinfunction "QG_6") (pintype "tri_state"))
    )
    (net (code "47") (name "EX7") (class "Default")
      (node (ref "IC12") (pin "7") (pinfunction "QH_7") (pintype "tri_state"))
    )
    (net (code "48") (name "GNC{slash}GLP_MODE") (class "Default")
      (node (ref "C1") (pin "1") (pinfunction "1_1") (pintype "passive"))
      (node (ref "D2") (pin "C") (pinfunction "C_C") (pintype "passive"))
    )
    (net (code "49") (name "GND") (class "Default")
      (node (ref "1K-1%") (pin "2") (pinfunction "2_2") (pintype "passive"))
      (node (ref "C1") (pin "2") (pinfunction "2_2") (pintype "passive"))
      (node (ref "C10") (pin "-") (pinfunction "-_-") (pintype "passive"))
      (node (ref "C16") (pin "2") (pinfunction "2_2") (pintype "passive"))
      (node (ref "C17") (pin "2") (pinfunction "2_2") (pintype "passive"))
      (node (ref "C18") (pin "2") (pinfunction "2_2") (pintype "passive"))
      (node (ref "C19") (pin "2") (pinfunction "2_2") (pintype "passive"))
      (node (ref "C2") (pin "2") (pinfunction "2_2") (pintype "passive"))
      (node (ref "C20") (pin "2") (pinfunction "2_2") (pintype "passive"))
      (node (ref "C21") (pin "2") (pinfunction "2_2") (pintype "passive"))
      (node (ref "C22") (pin "2") (pinfunction "2_2") (pintype "passive"))
      (node (ref "C23") (pin "2") (pinfunction "2_2") (pintype "passive"))
      (node (ref "C24") (pin "2") (pinfunction "2_2") (pintype "passive"))
      (node (ref "C25") (pin "2") (pinfunction "2_2") (pintype "passive"))
      (node (ref "C26") (pin "2") (pinfunction "2_2") (pintype "passive"))
      (node (ref "C27") (pin "2") (pinfunction "2_2") (pintype "passive"))
      (node (ref "C28") (pin "2") (pinfunction "2_2") (pintype "passive"))
      (node (ref "C29") (pin "2") (pinfunction "2_2") (pintype "passive"))
      (node (ref "C3") (pin "-") (pinfunction "-_-") (pintype "passive"))
      (node (ref "C30") (pin "2") (pinfunction "2_2") (pintype "passive"))
      (node (ref "C31") (pin "2") (pinfunction "2_2") (pintype "passive"))
      (node (ref "C7") (pin "2") (pinfunction "2_2") (pintype "passive"))
      (node (ref "C8") (pin "2") (pinfunction "2_2") (pintype "passive"))
      (node (ref "C9") (pin "2") (pinfunction "2_2") (pintype "passive"))
      (node (ref "D1") (pin "A") (pinfunction "A_A") (pintype "passive"))
      (node (ref "D12") (pin "A") (pinfunction "A_A") (pintype "passive"))
      (node (ref "D14") (pin "A") (pinfunction "A_A") (pintype "passive"))
      (node (ref "D16") (pin "A") (pinfunction "A_A") (pintype "passive"))
      (node (ref "D17") (pin "A") (pinfunction "A_A") (pintype "passive"))
      (node (ref "D18") (pin "A") (pinfunction "A_A") (pintype "passive"))
      (node (ref "D19") (pin "A") (pinfunction "A_A") (pintype "passive"))
      (node (ref "D2") (pin "A") (pinfunction "A_A") (pintype "passive"))
      (node (ref "D20") (pin "A") (pinfunction "A_A") (pintype "passive"))
      (node (ref "D22") (pin "A") (pinfunction "A_A") (pintype "passive"))
      (node (ref "D24") (pin "A") (pinfunction "A_A") (pintype "passive"))
      (node (ref "D27") (pin "A") (pinfunction "A_A") (pintype "passive"))
      (node (ref "D28") (pin "A") (pinfunction "A_A") (pintype "passive"))
      (node (ref "D29") (pin "A") (pinfunction "A_A") (pintype "passive"))
      (node (ref "D3") (pin "A") (pinfunction "A_A") (pintype "passive"))
      (node (ref "D32") (pin "A") (pinfunction "A_A") (pintype "passive"))
      (node (ref "D4") (pin "A") (pinfunction "A_A") (pintype "passive"))
      (node (ref "D5") (pin "A") (pinfunction "A_A") (pintype "passive"))
      (node (ref "D6") (pin "A") (pinfunction "A_A") (pintype "passive"))
      (node (ref "D7") (pin "A") (pinfunction "A_A") (pintype "passive"))
      (node (ref "D8") (pin "A") (pinfunction "A_A") (pintype "passive"))
      (node (ref "D9") (pin "A") (pinfunction "A_A") (pintype "passive"))
      (node (ref "DISPLAY") (pin "1") (pinfunction "1_1") (pintype "passive"))
      (node (ref "IC11") (pin "10") (pinfunction "SCL_10") (pintype "input"))
      (node (ref "IC11") (pin "13") (pinfunction "G_13") (pintype "input"))
      (node (ref "IC11") (pin "8") (pinfunction "GND_8") (pintype "power_in"))
      (node (ref "IC12") (pin "10") (pinfunction "SCL_10") (pintype "input"))
      (node (ref "IC12") (pin "13") (pinfunction "G_13") (pintype "input"))
      (node (ref "IC12") (pin "8") (pinfunction "GND_8") (pintype "power_in"))
      (node (ref "IC2") (pin "4") (pinfunction "V-_4") (pintype "power_in"))
      (node (ref "IC3") (pin "12") (pinfunction "VSS_12") (pintype "power_in"))
      (node (ref "IC3") (pin "15") (pinfunction "INH_15") (pintype "input"))
      (node (ref "IC4") (pin "3") (pinfunction "GND_3") (pintype "power_in"))
      (node (ref "IC4") (pin "5") (pinfunction "EN_5") (pintype "input"))
      (node (ref "IC4") (pin "6") (pinfunction "GND_6") (pintype "power_in"))
      (node (ref "IC5") (pin "8") (pinfunction "VSS_8") (pintype "power_in"))
      (node (ref "IC8") (pin "1") (pinfunction "A0_1") (pintype "input"))
      (node (ref "IC8") (pin "2") (pinfunction "A1_2") (pintype "input"))
      (node (ref "IC8") (pin "3") (pinfunction "A2_3") (pintype "input"))
      (node (ref "IC8") (pin "4") (pinfunction "GND_4") (pintype "power_in"))
      (node (ref "IC9") (pin "4") (pinfunction "V-_4") (pintype "power_in"))
      (node (ref "PROG") (pin "1") (pinfunction "1_1") (pintype "passive"))
      (node (ref "Q1") (pin "3") (pinfunction "E_3") (pintype "passive"))
      (node (ref "Q10") (pin "3") (pinfunction "E_3") (pintype "passive"))
      (node (ref "Q11") (pin "3") (pinfunction "E_3") (pintype "passive"))
      (node (ref "Q13") (pin "3") (pinfunction "E_3") (pintype "passive"))
      (node (ref "Q15") (pin "3") (pinfunction "E_3") (pintype "passive"))
      (node (ref "Q16") (pin "3") (pinfunction "E_3") (pintype "passive"))
      (node (ref "Q17") (pin "3") (pinfunction "E_3") (pintype "passive"))
      (node (ref "Q2") (pin "E") (pinfunction "E_E") (pintype "passive"))
      (node (ref "Q3") (pin "3") (pinfunction "E_3") (pintype "passive"))
      (node (ref "Q5") (pin "3") (pinfunction "E_3") (pintype "passive"))
      (node (ref "Q7") (pin "3") (pinfunction "E_3") (pintype "passive"))
      (node (ref "Q9") (pin "3") (pinfunction "E_3") (pintype "passive"))
      (node (ref "R2") (pin "1") (pinfunction "1_1") (pintype "passive"))
      (node (ref "R26") (pin "2") (pinfunction "2_2") (pintype "passive"))
      (node (ref "R29") (pin "2") (pinfunction "2_2") (pintype "passive"))
      (node (ref "R8") (pin "1") (pinfunction "1_1") (pintype "passive"))
      (node (ref "SJ1") (pin "2") (pinfunction "2_2") (pintype "passive"))
      (node (ref "SV1") (pin "1") (pinfunction "1_1") (pintype "passive"))
      (node (ref "SV2") (pin "1") (pinfunction "1_1") (pintype "passive"))
      (node (ref "SV3") (pin "1") (pinfunction "1_1") (pintype "passive"))
      (node (ref "SV3") (pin "2") (pinfunction "2_2") (pintype "passive"))
      (node (ref "U$2") (pin "GND_1") (pinfunction "GND_GND_1") (pintype "bidirectional"))
      (node (ref "U$2") (pin "GND_2") (pinfunction "GND_GND_2") (pintype "bidirectional"))
      (node (ref "U$2") (pin "GND_3") (pinfunction "GND_GND_3") (pintype "power_in"))
      (node (ref "U1") (pin "21") (pinfunction "GND_21") (pintype "passive"))
      (node (ref "U1") (pin "3") (pinfunction "GND_2_3") (pintype "passive"))
      (node (ref "U1") (pin "5") (pinfunction "GND_3_5") (pintype "passive"))
    )
    (net (code "50") (name "IAC_A") (class "Default")
      (node (ref "SV4") (pin "4") (pinfunction "4_4") (pintype "passive"))
      (node (ref "X2") (pin "14") (pinfunction "14_14") (pintype "passive"))
    )
    (net (code "51") (name "IAC_B") (class "Default")
      (node (ref "SV4") (pin "3") (pinfunction "3_3") (pintype "passive"))
      (node (ref "X2") (pin "31") (pinfunction "31_31") (pintype "passive"))
    )
    (net (code "52") (name "IAC_C") (class "Default")
      (node (ref "SV4") (pin "2") (pinfunction "2_2") (pintype "passive"))
      (node (ref "X2") (pin "48") (pinfunction "48_48") (pintype "passive"))
    )
    (net (code "53") (name "IAC_D") (class "Default")
      (node (ref "SV4") (pin "1") (pinfunction "1_1") (pintype "passive"))
      (node (ref "X2") (pin "15") (pinfunction "15_15") (pintype "passive"))
    )
    (net (code "54") (name "INY1") (class "Default")
      (node (ref "D1") (pin "C") (pinfunction "C_C") (pintype "passive"))
      (node (ref "P1") (pin "1") (pinfunction "1_1") (pintype "passive"))
      (node (ref "Q1") (pin "4") (pinfunction "C_4") (pintype "passive"))
    )
    (net (code "55") (name "INY2") (class "Default")
      (node (ref "D4") (pin "C") (pinfunction "C_C") (pintype "passive"))
      (node (ref "P1") (pin "2") (pinfunction "2_2") (pintype "passive"))
      (node (ref "Q3") (pin "4") (pinfunction "C_4") (pintype "passive"))
    )
    (net (code "56") (name "INY3") (class "Default")
      (node (ref "D6") (pin "C") (pinfunction "C_C") (pintype "passive"))
      (node (ref "P1") (pin "3") (pinfunction "3_3") (pintype "passive"))
      (node (ref "Q5") (pin "4") (pinfunction "C_4") (pintype "passive"))
    )
    (net (code "57") (name "INY4") (class "Default")
      (node (ref "D7") (pin "C") (pinfunction "C_C") (pintype "passive"))
      (node (ref "P1") (pin "4") (pinfunction "4_4") (pintype "passive"))
      (node (ref "Q7") (pin "4") (pinfunction "C_4") (pintype "passive"))
    )
    (net (code "58") (name "INYL1A") (class "Default")
      (node (ref "IC5") (pin "3") (pinfunction "I_3") (pintype "input"))
      (node (ref "U1") (pin "23") (pinfunction "PC0_23") (pintype "bidirectional"))
    )
    (net (code "59") (name "INYL2A") (class "Default")
      (node (ref "IC5") (pin "5") (pinfunction "I_5") (pintype "input"))
      (node (ref "U1") (pin "24") (pinfunction "PC1_24") (pintype "bidirectional"))
    )
    (net (code "60") (name "INYL3A") (class "Default")
      (node (ref "IC5") (pin "7") (pinfunction "I_7") (pintype "input"))
      (node (ref "U1") (pin "25") (pinfunction "PC2_25") (pintype "bidirectional"))
    )
    (net (code "61") (name "INYL4A") (class "Default")
      (node (ref "IC5") (pin "9") (pinfunction "I_9") (pintype "input"))
      (node (ref "U1") (pin "26") (pinfunction "PC3_26") (pintype "bidirectional"))
    )
    (net (code "62") (name "L1") (class "Default")
      (node (ref "R9") (pin "1") (pinfunction "1_1") (pintype "passive"))
    )
    (net (code "63") (name "L2") (class "Default")
      (node (ref "R10") (pin "1") (pinfunction "1_1") (pintype "passive"))
    )
    (net (code "64") (name "L3") (class "Default")
      (node (ref "R11") (pin "1") (pinfunction "1_1") (pintype "passive"))
    )
    (net (code "65") (name "L4") (class "Default")
      (node (ref "R12") (pin "1") (pinfunction "1_1") (pintype "passive"))
    )
    (net (code "66") (name "L5") (class "Default")
      (node (ref "R14") (pin "1") (pinfunction "1_1") (pintype "passive"))
      (node (ref "U$2") (pin "PA_5") (pinfunction "PA_5_PA_5") (pintype "bidirectional"))
    )
    (net (code "67") (name "LAMB0") (class "Default")
      (node (ref "R25") (pin "1") (pinfunction "1_1") (pintype "passive"))
    )
    (net (code "68") (name "LAMB0OUT") (class "Default")
      (node (ref "C17") (pin "1") (pinfunction "1_1") (pintype "passive"))
      (node (ref "IC3") (pin "23") (pinfunction "X8_23") (pintype "input"))
      (node (ref "IC9") (pin "1") (pinfunction "OUT_1") (pintype "output"))
      (node (ref "R27") (pin "2") (pinfunction "2_2") (pintype "passive"))
    )
    (net (code "69") (name "LAMB1") (class "Default")
      (node (ref "R28") (pin "1") (pinfunction "1_1") (pintype "passive"))
    )
    (net (code "70") (name "LAMB1OUT") (class "Default")
      (node (ref "C19") (pin "1") (pinfunction "1_1") (pintype "passive"))
      (node (ref "IC3") (pin "22") (pinfunction "X9_22") (pintype "input"))
      (node (ref "IC9") (pin "7") (pinfunction "OUT_7") (pintype "output"))
      (node (ref "R30") (pin "2") (pinfunction "2_2") (pintype "passive"))
    )
    (net (code "71") (name "LED1") (class "Default")
      (node (ref "Q2") (pin "C") (pinfunction "C_C") (pintype "passive"))
    )
    (net (code "72") (name "LED1A") (class "Default")
      (node (ref "R3") (pin "1") (pinfunction "1_1") (pintype "passive"))
    )
    (net (code "73") (name "M1") (class "Default")
      (node (ref "IC11") (pin "15") (pinfunction "QA_15") (pintype "tri_state"))
      (node (ref "SV3") (pin "6") (pinfunction "6_6") (pintype "passive"))
    )
    (net (code "74") (name "M2") (class "Default")
      (node (ref "IC11") (pin "1") (pinfunction "QB_1") (pintype "tri_state"))
      (node (ref "SV3") (pin "5") (pinfunction "5_5") (pintype "passive"))
    )
    (net (code "75") (name "M3") (class "Default")
      (node (ref "IC11") (pin "2") (pinfunction "QC_2") (pintype "tri_state"))
      (node (ref "SV3") (pin "4") (pinfunction "4_4") (pintype "passive"))
    )
    (net (code "76") (name "M4") (class "Default")
      (node (ref "IC11") (pin "3") (pinfunction "QD_3") (pintype "tri_state"))
      (node (ref "SV3") (pin "3") (pinfunction "3_3") (pintype "passive"))
    )
    (net (code "78") (name "MISO") (class "Default")
      (node (ref "U$2") (pin "PB_6") (pinfunction "PB_6_PB_6") (pintype "bidirectional"))
      (node (ref "U1") (pin "16") (pinfunction "PB4_16") (pintype "bidirectional"))
    )
    (net (code "79") (name "MOSI") (class "Default")
      (node (ref "U$2") (pin "PB_7") (pinfunction "PB_7_PB_7") (pintype "bidirectional"))
      (node (ref "U1") (pin "15") (pinfunction "PB3_15") (pintype "bidirectional"))
    )
    (net (code "80") (name "N$18_P") (class "Default")
      (node (ref "Q4") (pin "2") (pinfunction "2_2") (pintype "passive"))
      (node (ref "U1") (pin "7") (pinfunction "PB6_7") (pintype "bidirectional"))
    )
    (net (code "81") (name "N$20_N") (class "Default")
      (node (ref "Q4") (pin "1") (pinfunction "1_1") (pintype "passive"))
      (node (ref "U1") (pin "8") (pinfunction "PB7_8") (pintype "bidirectional"))
    )
    (net (code "82") (name "Net-(IC2A-+IN)") (class "Default")
      (node (ref "IC2") (pin "3") (pinfunction "+IN_3") (pintype "input"))
      (node (ref "R1") (pin "2") (pinfunction "2_2") (pintype "passive"))
      (node (ref "R2") (pin "2") (pinfunction "2_2") (pintype "passive"))
    )
    (net (code "83") (name "Net-(IC4-FB)") (class "Default")
      (node (ref "1K-1%") (pin "1") (pinfunction "1_1") (pintype "passive"))
      (node (ref "3K-1%") (pin "2") (pinfunction "2_2") (pintype "passive"))
      (node (ref "IC4") (pin "4") (pinfunction "FB_4") (pintype "input"))
    )
    (net (code "84") (name "Net-(IC4-OUT)") (class "Default")
      (node (ref "D9") (pin "C") (pinfunction "C_C") (pintype "passive"))
      (node (ref "IC4") (pin "2") (pinfunction "OUT_2") (pintype "output"))
      (node (ref "L1") (pin "1") (pinfunction "1_1") (pintype "passive"))
    )
    (net (code "85") (name "Net-(IC5A-O)") (class "Default")
      (node (ref "IC5") (pin "2") (pinfunction "O_2") (pintype "output"))
      (node (ref "Q1") (pin "1") (pinfunction "B_1") (pintype "passive"))
    )
    (net (code "86") (name "Net-(IC5B-O)") (class "Default")
      (node (ref "IC5") (pin "4") (pinfunction "O_4") (pintype "output"))
      (node (ref "Q3") (pin "1") (pinfunction "B_1") (pintype "passive"))
    )
    (net (code "87") (name "Net-(IC5C-O)") (class "Default")
      (node (ref "IC5") (pin "6") (pinfunction "O_6") (pintype "output"))
      (node (ref "Q5") (pin "1") (pinfunction "B_1") (pintype "passive"))
    )
    (net (code "88") (name "Net-(IC5D-O)") (class "Default")
      (node (ref "IC5") (pin "10") (pinfunction "O_10") (pintype "output"))
      (node (ref "Q7") (pin "1") (pinfunction "B_1") (pintype "passive"))
    )
    (net (code "89") (name "Net-(IC5E-O)") (class "Default")
      (node (ref "IC5") (pin "12") (pinfunction "O_12") (pintype "output"))
      (node (ref "Q11") (pin "1") (pinfunction "B_1") (pintype "passive"))
    )
    (net (code "90") (name "Net-(IC5F-O)") (class "Default")
      (node (ref "IC5") (pin "15") (pinfunction "O_15") (pintype "output"))
      (node (ref "Q13") (pin "1") (pinfunction "B_1") (pintype "passive"))
    )
    (net (code "91") (name "Net-(IC8-WP)") (class "Default")
      (node (ref "IC8") (pin "7") (pinfunction "WP_7") (pintype "input"))
      (node (ref "SJ1") (pin "1") (pinfunction "1_1") (pintype "passive"))
    )
    (net (code "92") (name "Net-(IC9A-+IN)") (class "Default")
      (node (ref "C16") (pin "1") (pinfunction "1_1") (pintype "passive"))
      (node (ref "IC9") (pin "3") (pinfunction "+IN_3") (pintype "input"))
      (node (ref "R25") (pin "2") (pinfunction "2_2") (pintype "passive"))
    )
    (net (code "93") (name "Net-(IC9A--IN)") (class "Default")
      (node (ref "IC9") (pin "2") (pinfunction "-IN_2") (pintype "input"))
      (node (ref "R26") (pin "1") (pinfunction "1_1") (pintype "passive"))
      (node (ref "R27") (pin "1") (pinfunction "1_1") (pintype "passive"))
    )
    (net (code "94") (name "Net-(IC9B-+IN)") (class "Default")
      (node (ref "C18") (pin "1") (pinfunction "1_1") (pintype "passive"))
      (node (ref "IC9") (pin "5") (pinfunction "+IN_5") (pintype "input"))
      (node (ref "R28") (pin "2") (pinfunction "2_2") (pintype "passive"))
    )
    (net (code "95") (name "Net-(IC9B--IN)") (class "Default")
      (node (ref "IC9") (pin "6") (pinfunction "-IN_6") (pintype "input"))
      (node (ref "R29") (pin "1") (pinfunction "1_1") (pintype "passive"))
      (node (ref "R30") (pin "1") (pinfunction "1_1") (pintype "passive"))
    )
    (net (code "96") (name "Net-(IC11A-QH*)") (class "Default")
      (node (ref "IC11") (pin "9") (pinfunction "QH*_9") (pintype "tri_state"))
      (node (ref "IC12") (pin "14") (pinfunction "SER_14") (pintype "input"))
    )
    (net (code "97") (name "Net-(LED1-C)") (class "Default")
      (node (ref "LED1") (pin "K") (pinfunction "C_K") (pintype "passive"))
      (node (ref "R9") (pin "2") (pinfunction "2_2") (pintype "passive"))
    )
    (net (code "98") (name "Net-(LED2-C)") (class "Default")
      (node (ref "LED2") (pin "K") (pinfunction "C_K") (pintype "passive"))
      (node (ref "R10") (pin "2") (pinfunction "2_2") (pintype "passive"))
    )
    (net (code "99") (name "Net-(LED3-C)") (class "Default")
      (node (ref "LED3") (pin "K") (pinfunction "C_K") (pintype "passive"))
      (node (ref "R11") (pin "2") (pinfunction "2_2") (pintype "passive"))
    )
    (net (code "100") (name "Net-(LED4-C)") (class "Default")
      (node (ref "LED4") (pin "K") (pinfunction "C_K") (pintype "passive"))
      (node (ref "R12") (pin "2") (pinfunction "2_2") (pintype "passive"))
    )
    (net (code "101") (name "Net-(LED5-C)") (class "Default")
      (node (ref "LED5") (pin "K") (pinfunction "C_K") (pintype "passive"))
      (node (ref "R14") (pin "2") (pinfunction "2_2") (pintype "passive"))
    )
    (net (code "102") (name "Net-(Q2-PadB)") (class "Default")
      (node (ref "Q2") (pin "B") (pinfunction "B_B") (pintype "passive"))
      (node (ref "R3") (pin "2") (pinfunction "2_2") (pintype "passive"))
    )
    (net (code "103") (name "Net-(Q9-B)") (class "Default")
      (node (ref "Q9") (pin "1") (pinfunction "B_1") (pintype "passive"))
      (node (ref "R16") (pin "2") (pinfunction "2_2") (pintype "passive"))
    )
    (net (code "104") (name "Net-(Q10-B)") (class "Default")
      (node (ref "Q10") (pin "1") (pinfunction "B_1") (pintype "passive"))
      (node (ref "R17") (pin "2") (pinfunction "2_2") (pintype "passive"))
    )
    (net (code "105") (name "Net-(Q15-B)") (class "Default")
      (node (ref "Q15") (pin "1") (pinfunction "B_1") (pintype "passive"))
      (node (ref "R20") (pin "2") (pinfunction "2_2") (pintype "passive"))
    )
    (net (code "106") (name "Net-(Q16-B)") (class "Default")
      (node (ref "Q16") (pin "1") (pinfunction "B_1") (pintype "passive"))
      (node (ref "R23") (pin "2") (pinfunction "2_2") (pintype "passive"))
    )
    (net (code "107") (name "Net-(Q17-B)") (class "Default")
      (node (ref "Q17") (pin "1") (pinfunction "B_1") (pintype "passive"))
      (node (ref "R21") (pin "2") (pinfunction "2_2") (pintype "passive"))
    )
    (net (code "108") (name "PWM") (class "Default")
      (node (ref "SV4") (pin "7") (pinfunction "7_7") (pintype "passive"))
      (node (ref "U1") (pin "1") (pinfunction "PD3_1") (pintype "bidirectional"))
    )
    (net (code "109") (name "RCK") (class "Default")
      (node (ref "IC11") (pin "12") (pinfunction "RCK_12") (pintype "input"))
      (node (ref "IC12") (pin "12") (pinfunction "RCK_12") (pintype "input"))
      (node (ref "U1") (pin "11") (pinfunction "PD7_11") (pintype "bidirectional"))
    )
    (net (code "110") (name "RL1") (class "Default")
      (node (ref "IC11") (pin "4") (pinfunction "QE_4") (pintype "tri_state"))
      (node (ref "R16") (pin "1") (pinfunction "1_1") (pintype "passive"))
    )
    (net (code "111") (name "RL1IN") (class "Default")
      (node (ref "D12") (pin "C") (pinfunction "C_C") (pintype "passive"))
      (node (ref "D13") (pin "A") (pinfunction "A_A") (pintype "passive"))
      (node (ref "Q9") (pin "4") (pinfunction "C_4") (pintype "passive"))
      (node (ref "X2") (pin "17") (pinfunction "17_17") (pintype "passive"))
    )
    (net (code "112") (name "RL2") (class "Default")
      (node (ref "IC11") (pin "5") (pinfunction "QF_5") (pintype "tri_state"))
      (node (ref "R17") (pin "1") (pinfunction "1_1") (pintype "passive"))
    )
    (net (code "113") (name "RL2IN") (class "Default")
      (node (ref "D14") (pin "C") (pinfunction "C_C") (pintype "passive"))
      (node (ref "D15") (pin "A") (pinfunction "A_A") (pintype "passive"))
      (node (ref "Q10") (pin "4") (pinfunction "C_4") (pintype "passive"))
      (node (ref "X2") (pin "33") (pinfunction "33_33") (pintype "passive"))
    )
    (net (code "114") (name "RL3") (class "Default")
      (node (ref "IC11") (pin "6") (pinfunction "QG_6") (pintype "tri_state"))
      (node (ref "R20") (pin "1") (pinfunction "1_1") (pintype "passive"))
    )
    (net (code "115") (name "RL3IN") (class "Default")
      (node (ref "D20") (pin "C") (pinfunction "C_C") (pintype "passive"))
      (node (ref "D21") (pin "A") (pinfunction "A_A") (pintype "passive"))
      (node (ref "Q15") (pin "4") (pinfunction "C_4") (pintype "passive"))
      (node (ref "X2") (pin "16") (pinfunction "16_16") (pintype "passive"))
    )
    (net (code "116") (name "RL4") (class "Default")
      (node (ref "IC11") (pin "7") (pinfunction "QH_7") (pintype "tri_state"))
      (node (ref "R23") (pin "1") (pinfunction "1_1") (pintype "passive"))
    )
    (net (code "117") (name "RL4IN") (class "Default")
      (node (ref "D22") (pin "C") (pinfunction "C_C") (pintype "passive"))
      (node (ref "D23") (pin "A") (pinfunction "A_A") (pintype "passive"))
      (node (ref "Q16") (pin "4") (pinfunction "C_4") (pintype "passive"))
      (node (ref "X2") (pin "49") (pinfunction "49_49") (pintype "passive"))
    )
    (net (code "118") (name "RL5") (class "Default")
      (node (ref "IC12") (pin "15") (pinfunction "QA_15") (pintype "tri_state"))
      (node (ref "R21") (pin "1") (pinfunction "1_1") (pintype "passive"))
    )
    (net (code "119") (name "RL5IN") (class "Default")
      (node (ref "D32") (pin "C") (pinfunction "C_C") (pintype "passive"))
      (node (ref "D33") (pin "A") (pinfunction "A_A") (pintype "passive"))
      (node (ref "Q17") (pin "4") (pinfunction "C_4") (pintype "passive"))
      (node (ref "X2") (pin "32") (pinfunction "32_32") (pintype "passive"))
    )
    (net (code "120") (name "RX") (class "Default")
      (node (ref "PROG") (pin "3") (pinfunction "3_3") (pintype "passive"))
      (node (ref "U$2") (pin "PA_9") (pinfunction "PA_9_PA_9") (pintype "bidirectional"))
    )
    (net (code "121") (name "SCK") (class "Default")
      (node (ref "U$2") (pin "PB_5") (pinfunction "PB_5_PB_5") (pintype "bidirectional"))
      (node (ref "U1") (pin "17") (pinfunction "PB5_17") (pintype "bidirectional"))
    )
    (net (code "122") (name "SCK2") (class "Default")
      (node (ref "IC11") (pin "11") (pinfunction "SCK_11") (pintype "input"))
      (node (ref "IC12") (pin "11") (pinfunction "SCK_11") (pintype "input"))
      (node (ref "U1") (pin "10") (pinfunction "PD6_10") (pintype "bidirectional"))
    )
    (net (code "123") (name "SCL") (class "Default")
      (node (ref "DISPLAY") (pin "4") (pinfunction "4_4") (pintype "passive"))
      (node (ref "IC8") (pin "6") (pinfunction "SCL_6") (pintype "input"))
      (node (ref "U$2") (pin "PB_10") (pinfunction "PB_10_PB_10") (pintype "bidirectional"))
    )
    (net (code "124") (name "SDA") (class "Default")
      (node (ref "DISPLAY") (pin "3") (pinfunction "3_3") (pintype "passive"))
      (node (ref "IC8") (pin "5") (pinfunction "SDA_5") (pintype "bidirectional"))
      (node (ref "U$2") (pin "PB_11") (pinfunction "PB_11_PB_11") (pintype "bidirectional"))
    )
    (net (code "125") (name "SER") (class "Default")
      (node (ref "IC11") (pin "14") (pinfunction "SER_14") (pintype "input"))
      (node (ref "U1") (pin "9") (pinfunction "PD5_9") (pintype "bidirectional"))
    )
    (net (code "126") (name "SS") (class "Default")
      (node (ref "U$2") (pin "PB_4") (pinfunction "PB_4_PB_4") (pintype "bidirectional"))
      (node (ref "U1") (pin "14") (pinfunction "PB2_14") (pintype "bidirectional"))
    )
    (net (code "130") (name "TPSM_A") (class "Default")
      (node (ref "SV4") (pin "6") (pinfunction "6_6") (pintype "passive"))
      (node (ref "X2") (pin "30") (pinfunction "30_30") (pintype "passive"))
    )
    (net (code "131") (name "TPSM_B") (class "Default")
      (node (ref "SV4") (pin "5") (pinfunction "5_5") (pintype "passive"))
      (node (ref "X2") (pin "47") (pinfunction "47_47") (pintype "passive"))
    )
    (net (code "132") (name "TX") (class "Default")
      (node (ref "PROG") (pin "2") (pinfunction "2_2") (pintype "passive"))
      (node (ref "U$2") (pin "PA_10") (pinfunction "PA_10_PA_10") (pintype "bidirectional"))
    )
    (net (code "133") (name "VBAT") (class "Default")
      (node (ref "D27") (pin "C") (pinfunction "C_C") (pintype "passive"))
      (node (ref "IC3") (pin "21") (pinfunction "X10_21") (pintype "input"))
      (node (ref "R7") (pin "1") (pinfunction "1_1") (pintype "passive"))
      (node (ref "R8") (pin "2") (pinfunction "2_2") (pintype "passive"))
    )
    (net (code "134") (name "unconnected-(IC12A-QH*-Pad9)") (class "Default")
      (node (ref "IC12") (pin "9") (pinfunction "QH*_9") (pintype "tri_state"))
    )
    (net (code "135") (name "unconnected-(U$2-3.3V-Pad3.3V_2)") (class "Default")
      (node (ref "U$2") (pin "3.3V_2") (pinfunction "3.3V_3.3V_2") (pintype "bidirectional"))
    )
    (net (code "136") (name "unconnected-(U$2-PadPA_1)") (class "Default")
      (node (ref "U$2") (pin "PA_1") (pinfunction "PA_1_PA_1") (pintype "bidirectional"))
    )
    (net (code "137") (name "unconnected-(U$2-PadPA_2)") (class "Default")
      (node (ref "U$2") (pin "PA_2") (pinfunction "PA_2_PA_2") (pintype "bidirectional"))
    )
    (net (code "138") (name "unconnected-(U$2-PadPA_3)") (class "Default")
      (node (ref "U$2") (pin "PA_3") (pinfunction "PA_3_PA_3") (pintype "bidirectional"))
    )
    (net (code "139") (name "unconnected-(U$2-PadPA_4)") (class "Default")
      (node (ref "U$2") (pin "PA_4") (pinfunction "PA_4_PA_4") (pintype "bidirectional"))
    )
    (net (code "140") (name "unconnected-(U$2-PadPA_8)") (class "Default")
      (node (ref "U$2") (pin "PA_8") (pinfunction "PA_8_PA_8") (pintype "bidirectional"))
    )
    (net (code "141") (name "unconnected-(U$2-PadPA_11)") (class "Default")
      (node (ref "U$2") (pin "PA_11") (pinfunction "PA_11_PA_11") (pintype "bidirectional"))
    )
    (net (code "142") (name "unconnected-(U$2-PadPA_12)") (class "Default")
      (node (ref "U$2") (pin "PA_12") (pinfunction "PA_12_PA_12") (pintype "bidirectional"))
    )
    (net (code "143") (name "unconnected-(U$2-PadPA_15)") (class "Default")
      (node (ref "U$2") (pin "PA_15") (pinfunction "PA_15_PA_15") (pintype "bidirectional"))
    )
    (net (code "144") (name "unconnected-(U$2-PadPB_3)") (class "Default")
      (node (ref "U$2") (pin "PB_3") (pinfunction "PB_3_PB_3") (pintype "bidirectional"))
    )
    (net (code "145") (name "unconnected-(U$2-PadPB_8)") (class "Default")
      (node (ref "U$2") (pin "PB_8") (pinfunction "PB_8_PB_8") (pintype "bidirectional"))
    )
    (net (code "146") (name "unconnected-(U$2-PadPB_9)") (class "Default")
      (node (ref "U$2") (pin "PB_9") (pinfunction "PB_9_PB_9") (pintype "bidirectional"))
    )
    (net (code "147") (name "unconnected-(U$2-PadPB_12)") (class "Default")
      (node (ref "U$2") (pin "PB_12") (pinfunction "PB_12_PB_12") (pintype "bidirectional"))
    )
    (net (code "148") (name "unconnected-(U$2-PadPB_13)") (class "Default")
      (node (ref "U$2") (pin "PB_13") (pinfunction "PB_13_PB_13") (pintype "bidirectional"))
    )
    (net (code "149") (name "unconnected-(U$2-PadPB_14)") (class "Default")
      (node (ref "U$2") (pin "PB_14") (pinfunction "PB_14_PB_14") (pintype "bidirectional"))
    )
    (net (code "150") (name "unconnected-(U$2-PadPB_15)") (class "Default")
      (node (ref "U$2") (pin "PB_15") (pinfunction "PB_15_PB_15") (pintype "bidirectional"))
    )
    (net (code "151") (name "unconnected-(U$2-PadPC_13)") (class "Default")
      (node (ref "U$2") (pin "PC_13") (pinfunction "PC_13_PC_13") (pintype "bidirectional"))
    )
    (net (code "152") (name "unconnected-(U$2-PadPC_14)") (class "Default")
      (node (ref "U$2") (pin "PC_14") (pinfunction "PC_14_PC_14") (pintype "bidirectional"))
    )
    (net (code "153") (name "unconnected-(U$2-PadPC_15)") (class "Default")
      (node (ref "U$2") (pin "PC_15") (pinfunction "PC_15_PC_15") (pintype "bidirectional"))
    )
    (net (code "154") (name "unconnected-(U$2-PadRESET)") (class "Default")
      (node (ref "U$2") (pin "RESET") (pinfunction "RESET_RESET") (pintype "bidirectional"))
    )
    (net (code "155") (name "unconnected-(U$2-PadVB)") (class "Default")
      (node (ref "U$2") (pin "VB") (pinfunction "VB_VB") (pintype "bidirectional"))
    )
    (net (code "156") (name "unconnected-(U1-ADC6-Pad19)") (class "Default")
      (node (ref "U1") (pin "19") (pinfunction "ADC6_19") (pintype "input"))
    )
    (net (code "157") (name "unconnected-(U1-ADC7-Pad22)") (class "Default")
      (node (ref "U1") (pin "22") (pinfunction "ADC7_22") (pintype "input"))
    )
    (net (code "158") (name "unconnected-(U1-PB0-Pad12)") (class "Default")
      (node (ref "U1") (pin "12") (pinfunction "PB0_12") (pintype "bidirectional"))
    )
    (net (code "159") (name "unconnected-(U1-PB1-Pad13)") (class "Default")
      (node (ref "U1") (pin "13") (pinfunction "PB1_13") (pintype "bidirectional"))
    )
    (net (code "160") (name "unconnected-(U1-PC6-Pad29)") (class "Default")
      (node (ref "U1") (pin "29") (pinfunction "PC6_29") (pintype "bidirectional"))
    )
    (net (code "161") (name "unconnected-(U1-PD0-Pad30)") (class "Default")
      (node (ref "U1") (pin "30") (pinfunction "PD0_30") (pintype "bidirectional"))
    )
    (net (code "162") (name "unconnected-(U1-PD1-Pad31)") (class "Default")
      (node (ref "U1") (pin "31") (pinfunction "PD1_31") (pintype "bidirectional"))
    )
    (net (code "163") (name "unconnected-(U1-PD4-Pad2)") (class "Default")
      (node (ref "U1") (pin "2") (pinfunction "PD4_2") (pintype "bidirectional"))
    )
    (net (code "164") (name "unconnected-(X2-Pad1)") (class "Default")
      (node (ref "X2") (pin "1") (pinfunction "1_1") (pintype "passive"))
    )
    (net (code "165") (name "unconnected-(X2-Pad2)") (class "Default")
      (node (ref "X2") (pin "2") (pinfunction "2_2") (pintype "passive"))
    )
    (net (code "166") (name "unconnected-(X2-Pad3)") (class "Default")
      (node (ref "X2") (pin "3") (pinfunction "3_3") (pintype "passive"))
    )
    (net (code "167") (name "unconnected-(X2-Pad4)") (class "Default")
      (node (ref "X2") (pin "4") (pinfunction "4_4") (pintype "passive"))
    )
    (net (code "168") (name "unconnected-(X2-Pad5)") (class "Default")
      (node (ref "X2") (pin "5") (pinfunction "5_5") (pintype "passive"))
    )
    (net (code "169") (name "unconnected-(X2-Pad6)") (class "Default")
      (node (ref "X2") (pin "6") (pinfunction "6_6") (pintype "passive"))
    )
    (net (code "170") (name "unconnected-(X2-Pad7)") (class "Default")
      (node (ref "X2") (pin "7") (pinfunction "7_7") (pintype "passive"))
    )
    (net (code "171") (name "unconnected-(X2-Pad8)") (class "Default")
      (node (ref "X2") (pin "8") (pinfunction "8_8") (pintype "passive"))
    )
    (net (code "172") (name "unconnected-(X2-Pad9)") (class "Default")
      (node (ref "X2") (pin "9") (pinfunction "9_9") (pintype "passive"))
    )
    (net (code "173") (name "unconnected-(X2-Pad10)") (class "Default")
      (node (ref "X2") (pin "10") (pinfunction "10_10") (pintype "passive"))
    )
    (net (code "174") (name "unconnected-(X2-Pad11)") (class "Default")
      (node (ref "X2") (pin "11") (pinfunction "11_11") (pintype "passive"))
    )
    (net (code "175") (name "unconnected-(X2-Pad18)") (class "Default")
      (node (ref "X2") (pin "18") (pinfunction "18_18") (pintype "passive"))
    )
    (net (code "176") (name "unconnected-(X2-Pad19)") (class "Default")
      (node (ref "X2") (pin "19") (pinfunction "19_19") (pintype "passive"))
    )
    (net (code "177") (name "unconnected-(X2-Pad20)") (class "Default")
      (node (ref "X2") (pin "20") (pinfunction "20_20") (pintype "passive"))
    )
    (net (code "178") (name "unconnected-(X2-Pad21)") (class "Default")
      (node (ref "X2") (pin "21") (pinfunction "21_21") (pintype "passive"))
    )
    (net (code "179") (name "unconnected-(X2-Pad22)") (class "Default")
      (node (ref "X2") (pin "22") (pinfunction "22_22") (pintype "passive"))
    )
    (net (code "180") (name "unconnected-(X2-Pad23)") (class "Default")
      (node (ref "X2") (pin "23") (pinfunction "23_23") (pintype "passive"))
    )
    (net (code "181") (name "unconnected-(X2-Pad24)") (class "Default")
      (node (ref "X2") (pin "24") (pinfunction "24_24") (pintype "passive"))
    )
    (net (code "182") (name "unconnected-(X2-Pad25)") (class "Default")
      (node (ref "X2") (pin "25") (pinfunction "25_25") (pintype "passive"))
    )
    (net (code "183") (name "unconnected-(X2-Pad26)") (class "Default")
      (node (ref "X2") (pin "26") (pinfunction "26_26") (pintype "passive"))
    )
    (net (code "184") (name "unconnected-(X2-Pad27)") (class "Default")
      (node (ref "X2") (pin "27") (pinfunction "27_27") (pintype "passive"))
    )
    (net (code "185") (name "unconnected-(X2-Pad28)") (class "Default")
      (node (ref "X2") (pin "28") (pinfunction "28_28") (pintype "passive"))
    )
    (net (code "186") (name "unconnected-(X2-Pad34)") (class "Default")
      (node (ref "X2") (pin "34") (pinfunction "34_34") (pintype "passive"))
    )
    (net (code "187") (name "unconnected-(X2-Pad35)") (class "Default")
      (node (ref "X2") (pin "35") (pinfunction "35_35") (pintype "passive"))
    )
    (net (code "188") (name "unconnected-(X2-Pad36)") (class "Default")
      (node (ref "X2") (pin "36") (pinfunction "36_36") (pintype "passive"))
    )
    (net (code "189") (name "unconnected-(X2-Pad37)") (class "Default")
      (node (ref "X2") (pin "37") (pinfunction "37_37") (pintype "passive"))
    )
    (net (code "190") (name "unconnected-(X2-Pad38)") (class "Default")
      (node (ref "X2") (pin "38") (pinfunction "38_38") (pintype "passive"))
    )
    (net (code "191") (name "unconnected-(X2-Pad39)") (class "Default")
      (node (ref "X2") (pin "39") (pinfunction "39_39") (pintype "passive"))
    )
    (net (code "192") (name "unconnected-(X2-Pad40)") (class "Default")
      (node (ref "X2") (pin "40") (pinfunction "40_40") (pintype "passive"))
    )
    (net (code "193") (name "unconnected-(X2-Pad41)") (class "Default")
      (node (ref "X2") (pin "41") (pinfunction "41_41") (pintype "passive"))
    )
    (net (code "194") (name "unconnected-(X2-Pad42)") (class "Default")
      (node (ref "X2") (pin "42") (pinfunction "42_42") (pintype "passive"))
    )
    (net (code "195") (name "unconnected-(X2-Pad43)") (class "Default")
      (node (ref "X2") (pin "43") (pinfunction "43_43") (pintype "passive"))
    )
    (net (code "196") (name "unconnected-(X2-Pad44)") (class "Default")
      (node (ref "X2") (pin "44") (pinfunction "44_44") (pintype "passive"))
    )
    (net (code "197") (name "unconnected-(X2-Pad45)") (class "Default")
      (node (ref "X2") (pin "45") (pinfunction "45_45") (pintype "passive"))
    )
    (net (code "198") (name "unconnected-(X2-Pad46)") (class "Default")
      (node (ref "X2") (pin "46") (pinfunction "46_46") (pintype "passive"))
    )
    (net (code "199") (name "unconnected-(X2-PadG1)") (class "Default")
      (node (ref "X2") (pin "G1") (pinfunction "G1_G1") (pintype "passive"))
    )
    (net (code "200") (name "unconnected-(X2-PadG2)") (class "Default")
      (node (ref "X2") (pin "G2") (pinfunction "G2_G2") (pintype "passive"))
    )
  )
)
